# Laser_Teensy_No_AudShield.net
KiCad netlist of a schematic drawn in EAGLE
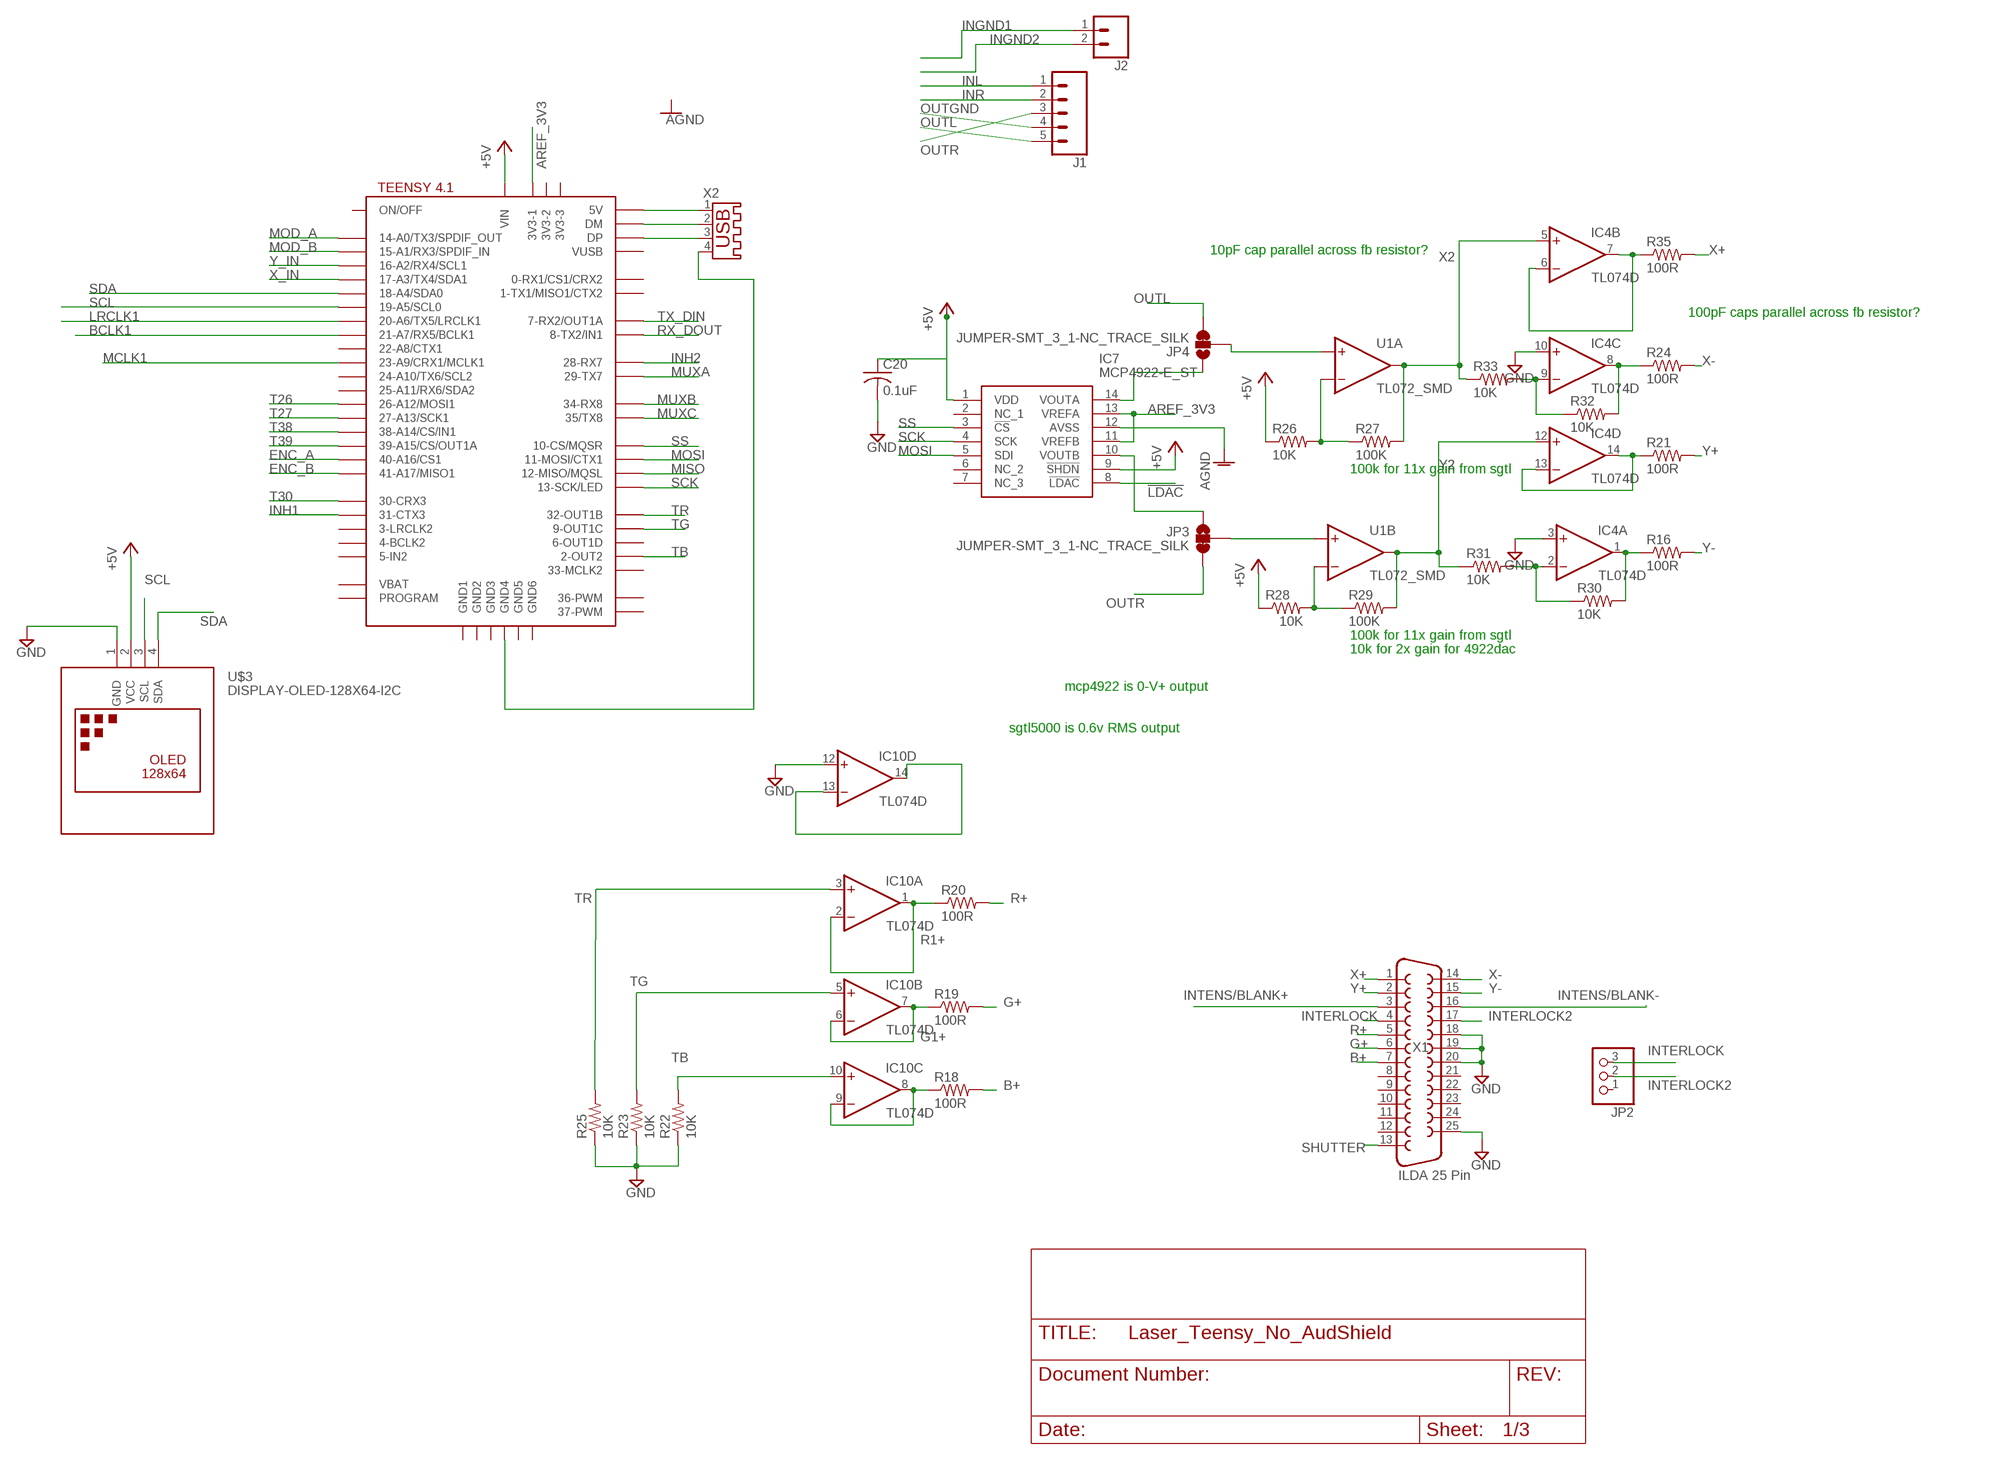
[diagram p0: schematic, sheet 1]
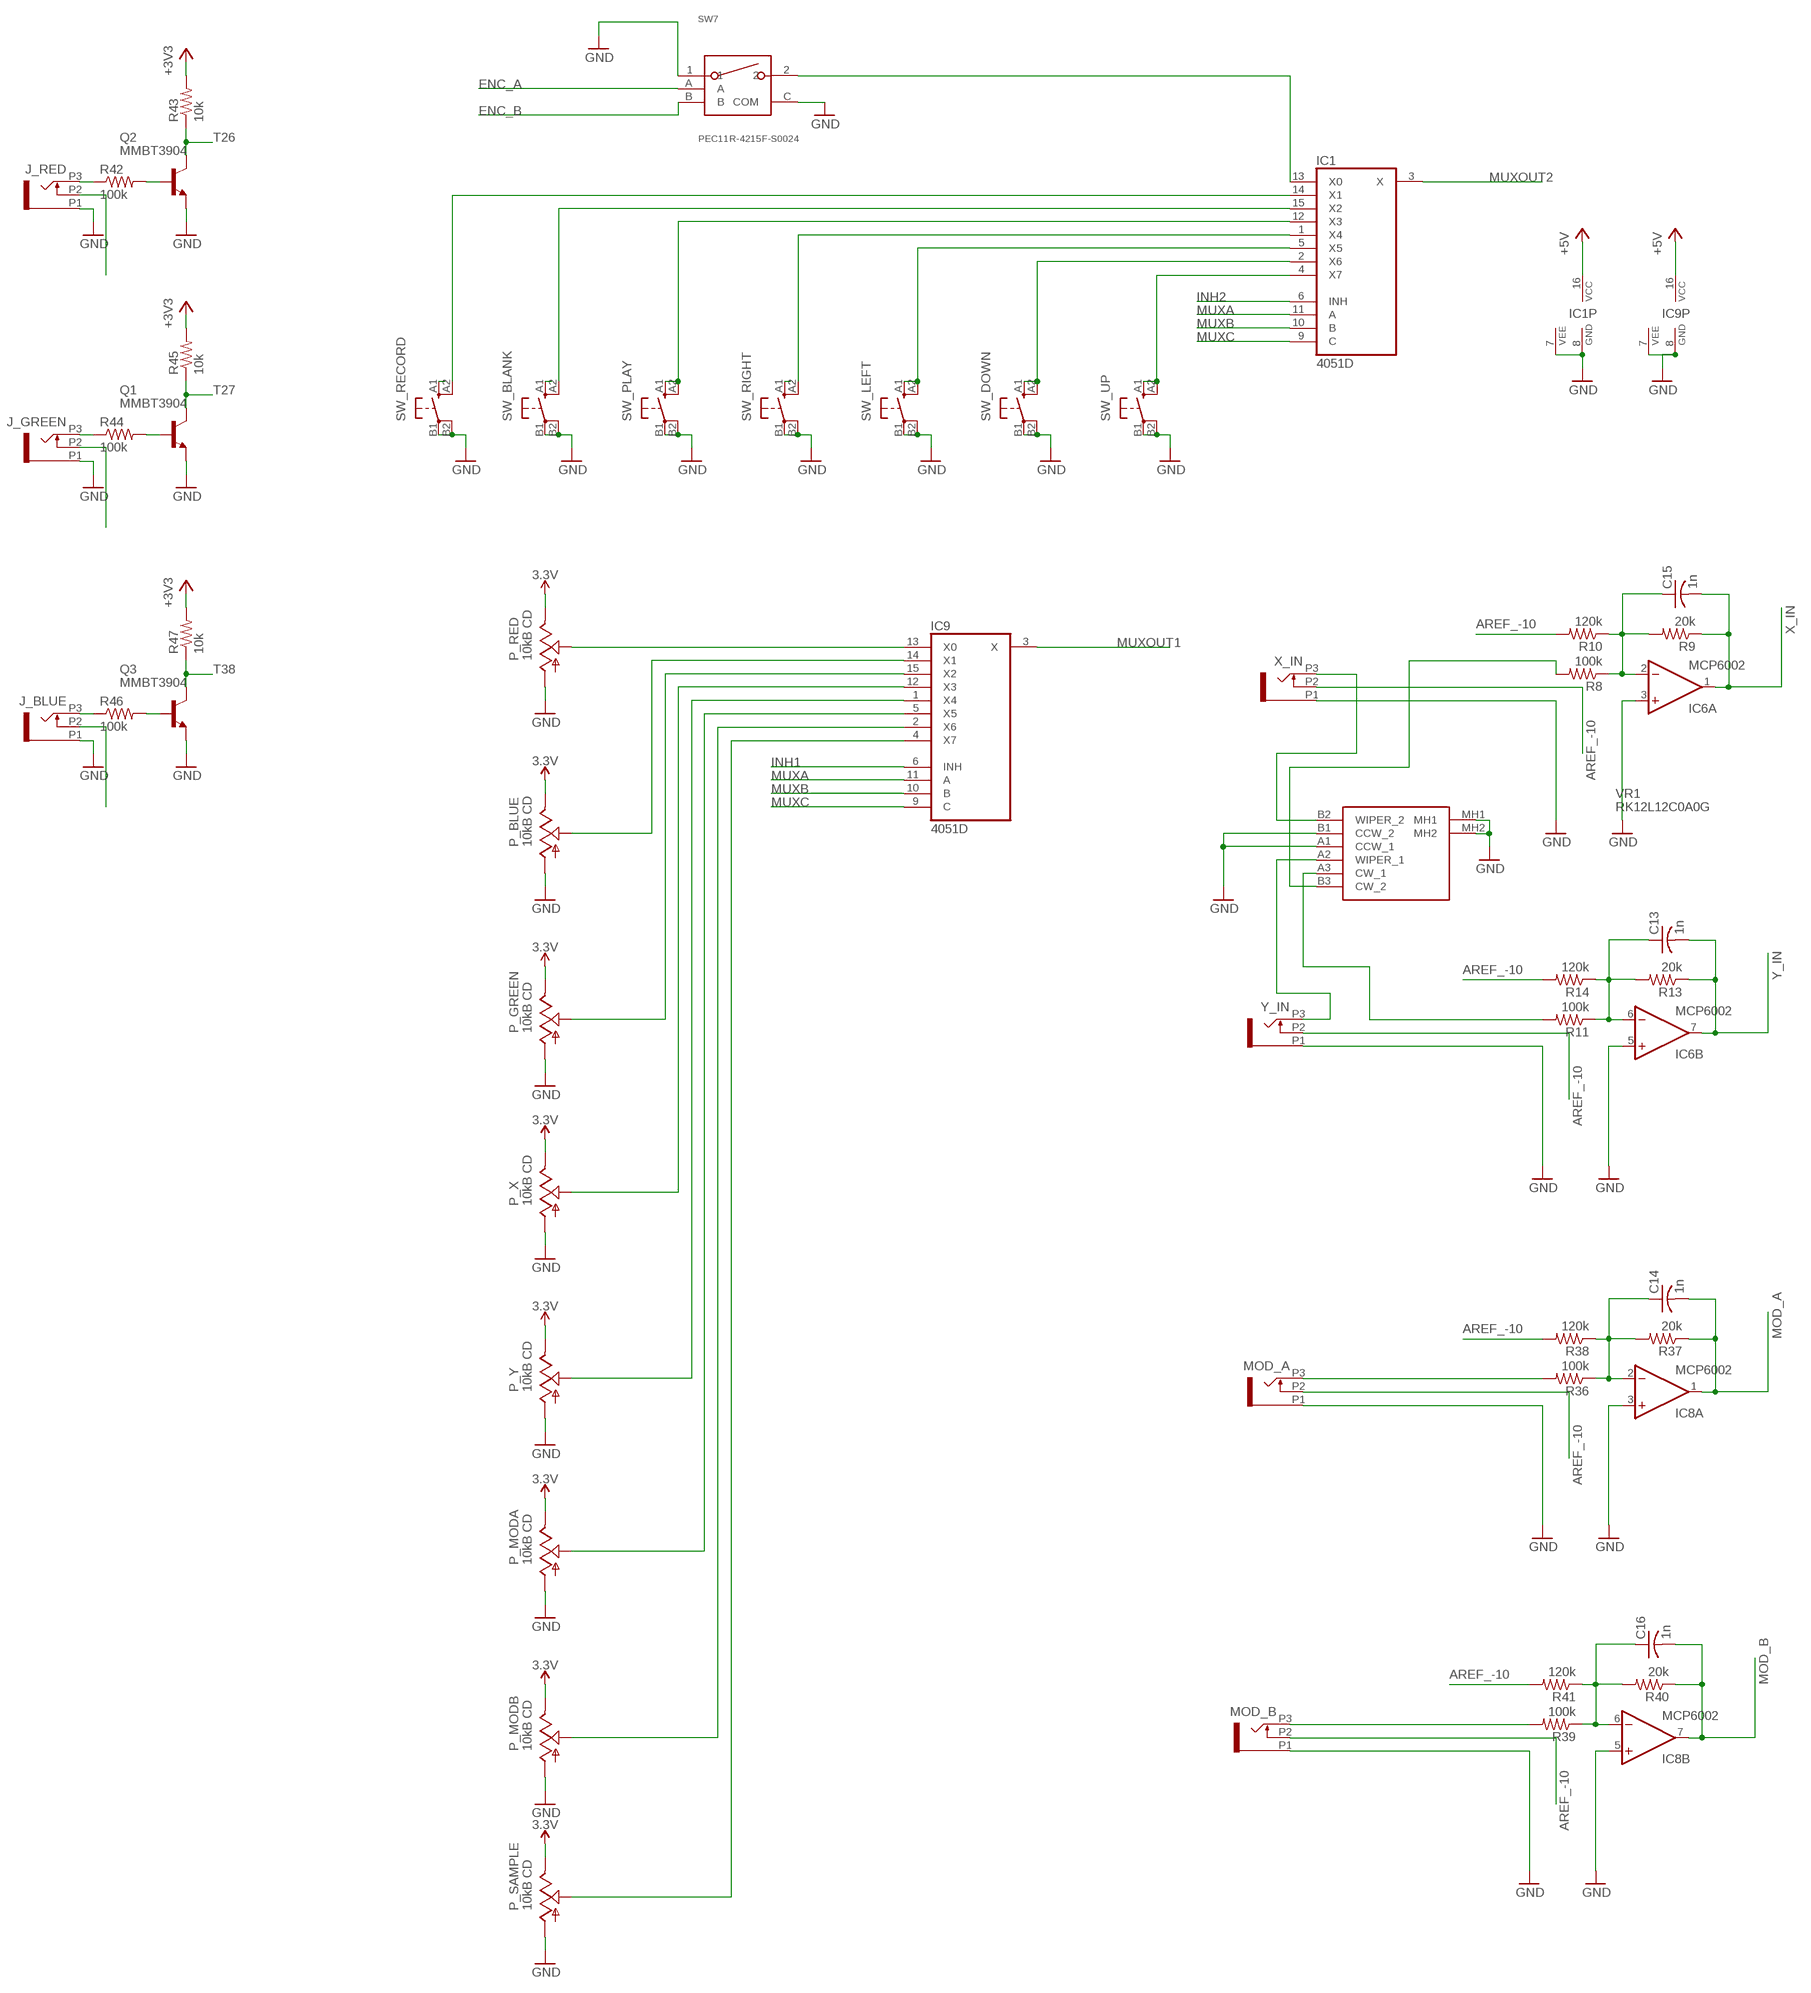
[diagram p1: schematic, sheet 2]
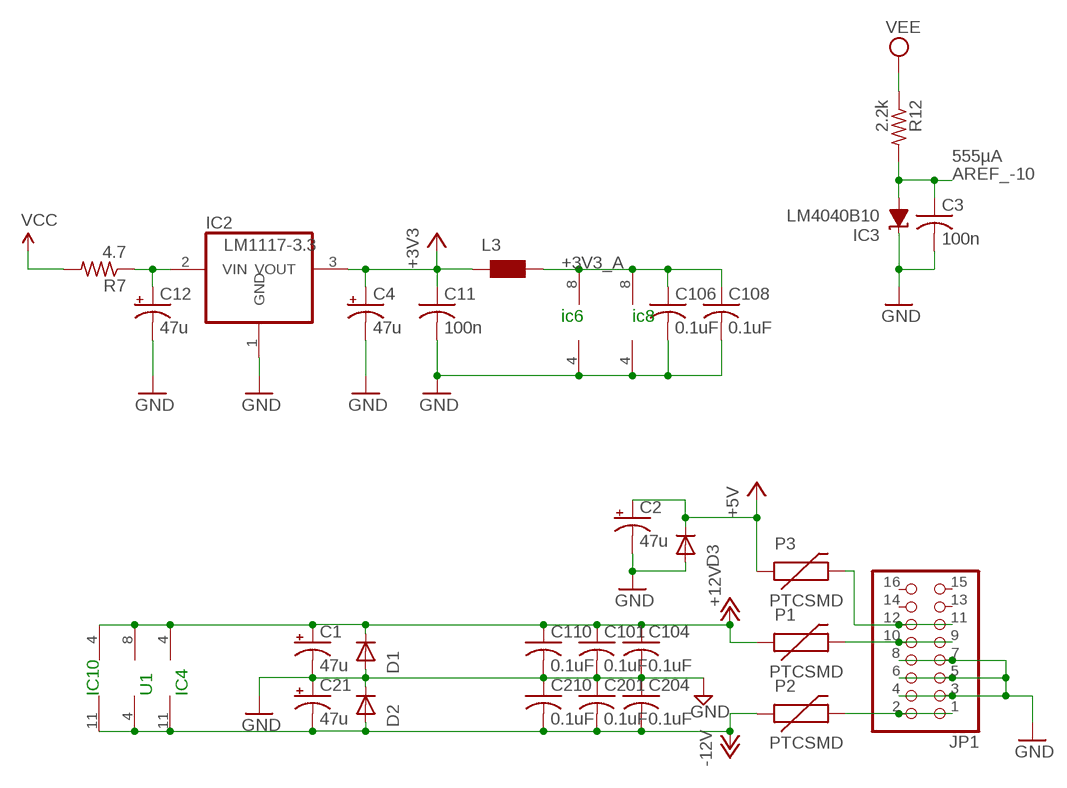
[diagram p2: schematic, sheet 3]

(export (version "E")
  (design (tool "Eeschema 10.0.6"))
  (components
    (comp (ref "C13")
      (value "1n")
      (footprint "eagle-import:C050-025X075")
      (libsource (lib "eagle-import") (part "rcl_334_C-US050-025X075"))
    )
    (comp (ref "C14")
      (value "1n")
      (footprint "eagle-import:C050-025X075")
      (libsource (lib "eagle-import") (part "rcl_334_C-US050-025X075"))
    )
    (comp (ref "C15")
      (value "1n")
      (footprint "eagle-import:C050-025X075")
      (libsource (lib "eagle-import") (part "rcl_334_C-US050-025X075"))
    )
    (comp (ref "C16")
      (value "1n")
      (footprint "eagle-import:C050-025X075")
      (libsource (lib "eagle-import") (part "rcl_334_C-US050-025X075"))
    )
    (comp (ref "IC1")
      (value "4051D")
      (footprint "eagle-import:SO16")
      (libsource (lib "eagle-import") (part "4051D"))
    )
    (comp (ref "IC6")
      (value "MCP6002")
      (footprint "eagle-import:SO08")
      (libsource (lib "eagle-import") (part "TL072D"))
    )
    (comp (ref "IC8")
      (value "MCP6002")
      (footprint "eagle-import:SO08")
      (libsource (lib "eagle-import") (part "TL072D"))
    )
    (comp (ref "IC9")
      (value "4051D")
      (footprint "eagle-import:SO16")
      (libsource (lib "eagle-import") (part "4051D"))
    )
    (comp (ref "J_BLUE")
      (value "PJ301_THONKICONN6")
      (footprint "eagle-import:WQP_PJ_301M6")
      (libsource (lib "eagle-import") (part "PJ301_THONKICONN6"))
    )
    (comp (ref "J_GREEN")
      (value "PJ301_THONKICONN6")
      (footprint "eagle-import:WQP_PJ_301M6")
      (libsource (lib "eagle-import") (part "PJ301_THONKICONN6"))
    )
    (comp (ref "J_RED")
      (value "PJ301_THONKICONN6")
      (footprint "eagle-import:WQP_PJ_301M6")
      (libsource (lib "eagle-import") (part "PJ301_THONKICONN6"))
    )
    (comp (ref "MOD_A")
      (value "PJ301_THONKICONN6")
      (footprint "eagle-import:WQP_PJ_301M6")
      (libsource (lib "eagle-import") (part "og-pj301_variations_PJ301_THONKICONN6"))
    )
    (comp (ref "MOD_B")
      (value "PJ301_THONKICONN6")
      (footprint "eagle-import:WQP_PJ_301M6")
      (libsource (lib "eagle-import") (part "og-pj301_variations_PJ301_THONKICONN6"))
    )
    (comp (ref "P_BLUE")
      (value "10kB CD")
      (footprint "eagle-import:ALPS_POT_VERTICAL_PS")
      (libsource (lib "eagle-import") (part "POT_USVERTICAL_PS"))
    )
    (comp (ref "P_GREEN")
      (value "10kB CD")
      (footprint "eagle-import:ALPS_POT_VERTICAL_PS")
      (libsource (lib "eagle-import") (part "POT_USVERTICAL_PS"))
    )
    (comp (ref "P_MODA")
      (value "10kB CD")
      (footprint "eagle-import:ALPS_POT_VERTICAL_PS")
      (libsource (lib "eagle-import") (part "POT_USVERTICAL_PS"))
    )
    (comp (ref "P_MODB")
      (value "10kB CD")
      (footprint "eagle-import:ALPS_POT_VERTICAL_PS")
      (libsource (lib "eagle-import") (part "POT_USVERTICAL_PS"))
    )
    (comp (ref "P_RED")
      (value "10kB CD")
      (footprint "eagle-import:ALPS_POT_VERTICAL_PS")
      (libsource (lib "eagle-import") (part "POT_USVERTICAL_PS"))
    )
    (comp (ref "P_SAMPLE")
      (value "10kB CD")
      (footprint "eagle-import:ALPS_POT_VERTICAL_PS")
      (libsource (lib "eagle-import") (part "POT_USVERTICAL_PS"))
    )
    (comp (ref "P_X")
      (value "10kB CD")
      (footprint "eagle-import:ALPS_POT_VERTICAL_PS")
      (libsource (lib "eagle-import") (part "POT_USVERTICAL_PS"))
    )
    (comp (ref "P_Y")
      (value "10kB CD")
      (footprint "eagle-import:ALPS_POT_VERTICAL_PS")
      (libsource (lib "eagle-import") (part "POT_USVERTICAL_PS"))
    )
    (comp (ref "Q1")
      (value "MMBT3904")
      (footprint "eagle-import:SOT23-BEC")
      (libsource (lib "eagle-import") (part "-NPN-SOT23-BECMMBT3904LT1"))
    )
    (comp (ref "Q2")
      (value "MMBT3904")
      (footprint "eagle-import:SOT23-BEC")
      (libsource (lib "eagle-import") (part "-NPN-SOT23-BECMMBT3904LT1"))
    )
    (comp (ref "Q3")
      (value "MMBT3904")
      (footprint "eagle-import:SOT23-BEC")
      (libsource (lib "eagle-import") (part "-NPN-SOT23-BECMMBT3904LT1"))
    )
    (comp (ref "R8")
      (value "100k")
      (footprint "eagle-import:0204_7")
      (libsource (lib "eagle-import") (part "rcl_334_R-US_0204/7"))
    )
    (comp (ref "R9")
      (value "20k")
      (footprint "eagle-import:0204_7")
      (libsource (lib "eagle-import") (part "rcl_334_R-US_0204/7"))
    )
    (comp (ref "R10")
      (value "120k")
      (footprint "eagle-import:0204_7")
      (libsource (lib "eagle-import") (part "rcl_334_R-US_0204/7"))
    )
    (comp (ref "R11")
      (value "100k")
      (footprint "eagle-import:0204_7")
      (libsource (lib "eagle-import") (part "rcl_334_R-US_0204/7"))
    )
    (comp (ref "R13")
      (value "20k")
      (footprint "eagle-import:0204_7")
      (libsource (lib "eagle-import") (part "rcl_334_R-US_0204/7"))
    )
    (comp (ref "R14")
      (value "120k")
      (footprint "eagle-import:0204_7")
      (libsource (lib "eagle-import") (part "rcl_334_R-US_0204/7"))
    )
    (comp (ref "R36")
      (value "100k")
      (footprint "eagle-import:0204_7")
      (libsource (lib "eagle-import") (part "rcl_334_R-US_0204/7"))
    )
    (comp (ref "R37")
      (value "20k")
      (footprint "eagle-import:0204_7")
      (libsource (lib "eagle-import") (part "rcl_334_R-US_0204/7"))
    )
    (comp (ref "R38")
      (value "120k")
      (footprint "eagle-import:0204_7")
      (libsource (lib "eagle-import") (part "rcl_334_R-US_0204/7"))
    )
    (comp (ref "R39")
      (value "100k")
      (footprint "eagle-import:0204_7")
      (libsource (lib "eagle-import") (part "rcl_334_R-US_0204/7"))
    )
    (comp (ref "R40")
      (value "20k")
      (footprint "eagle-import:0204_7")
      (libsource (lib "eagle-import") (part "rcl_334_R-US_0204/7"))
    )
    (comp (ref "R41")
      (value "120k")
      (footprint "eagle-import:0204_7")
      (libsource (lib "eagle-import") (part "rcl_334_R-US_0204/7"))
    )
    (comp (ref "R42")
      (value "100k")
      (footprint "eagle-import:R0603")
      (libsource (lib "eagle-import") (part "R-US_R0603"))
    )
    (comp (ref "R43")
      (value "10k")
      (footprint "eagle-import:R0603")
      (libsource (lib "eagle-import") (part "R-US_R0603"))
    )
    (comp (ref "R44")
      (value "100k")
      (footprint "eagle-import:R0603")
      (libsource (lib "eagle-import") (part "R-US_R0603"))
    )
    (comp (ref "R45")
      (value "10k")
      (footprint "eagle-import:R0603")
      (libsource (lib "eagle-import") (part "R-US_R0603"))
    )
    (comp (ref "R46")
      (value "100k")
      (footprint "eagle-import:R0603")
      (libsource (lib "eagle-import") (part "R-US_R0603"))
    )
    (comp (ref "R47")
      (value "10k")
      (footprint "eagle-import:R0603")
      (libsource (lib "eagle-import") (part "R-US_R0603"))
    )
    (comp (ref "SW7")
      (value "PEC11R-4215F-S0024")
      (footprint "eagle-import:PEC11R-4215F-S0024")
      (fields
        (field (name "DIGIKEY_PART_NUMBER") "PEC11R-4215F-S0024-ND")
        (field (name "MANUFACTURER") "Bourns Inc.")
        (field (name "CREATED_BY") "PCBLayout.com")
      )
      (libsource (lib "eagle-import") (part "PEC11R-4215F-S0024"))
    )
    (comp (ref "SW_BLANK")
      (value "D6R")
      (footprint "eagle-import:D6R")
      (libsource (lib "eagle-import") (part "D6R"))
    )
    (comp (ref "SW_DOWN")
      (value "D6R")
      (footprint "eagle-import:D6R")
      (libsource (lib "eagle-import") (part "D6R"))
    )
    (comp (ref "SW_LEFT")
      (value "D6R")
      (footprint "eagle-import:D6R")
      (libsource (lib "eagle-import") (part "D6R"))
    )
    (comp (ref "SW_PLAY")
      (value "D6R")
      (footprint "eagle-import:D6R")
      (libsource (lib "eagle-import") (part "D6R"))
    )
    (comp (ref "SW_RECORD")
      (value "D6R")
      (footprint "eagle-import:D6R")
      (libsource (lib "eagle-import") (part "D6R"))
    )
    (comp (ref "SW_RIGHT")
      (value "D6R")
      (footprint "eagle-import:D6R")
      (libsource (lib "eagle-import") (part "D6R"))
    )
    (comp (ref "SW_UP")
      (value "D6R")
      (footprint "eagle-import:D6R")
      (libsource (lib "eagle-import") (part "D6R"))
    )
    (comp (ref "VR1")
      (value "RK12L12C0A0G")
      (footprint "eagle-import:RK12L12C0A0G")
      (fields (field (name "MOUSER_PART_NUMBER") "688-RK12L12C0A0G"))
      (libsource (lib "eagle-import") (part "RK12L12C0A0G"))
    )
    (comp (ref "X_IN")
      (value "PJ301_THONKICONN6")
      (footprint "eagle-import:WQP_PJ_301M6")
      (libsource (lib "eagle-import") (part "og-pj301_variations_PJ301_THONKICONN6"))
    )
    (comp (ref "Y_IN")
      (value "PJ301_THONKICONN6")
      (footprint "eagle-import:WQP_PJ_301M6")
      (libsource (lib "eagle-import") (part "og-pj301_variations_PJ301_THONKICONN6"))
    )
    (comp (ref "C20")
      (value "0.1uF")
      (footprint "eagle-import:C0603")
      (libsource (lib "eagle-import") (part "C-USC0603"))
    )
    (comp (ref "IC4")
      (value "TL074D")
      (footprint "eagle-import:SO14")
      (libsource (lib "eagle-import") (part "TL074D"))
    )
    (comp (ref "IC7")
      (value "MCP4922-E_ST")
      (footprint "eagle-import:SOP65P638X110-14N")
      (fields
        (field (name "ARROW_PART_NUMBER") "MCP4922-E/ST")
        (field (name "MOUSER_PART_NUMBER") "579-MCP4922-E/ST")
      )
      (libsource (lib "eagle-import") (part "MCP4922-E_ST"))
    )
    (comp (ref "IC10")
      (value "TL074D")
      (footprint "eagle-import:SO14")
      (libsource (lib "eagle-import") (part "TL074D"))
    )
    (comp (ref "J1")
      (value "CONN_05")
      (footprint "eagle-import:1X05")
      (libsource (lib "eagle-import") (part "CONN_05"))
    )
    (comp (ref "J2")
      (value "CONN_02")
      (footprint "eagle-import:1X02")
      (libsource (lib "eagle-import") (part "CONN_02"))
    )
    (comp (ref "JP2")
      (value "PINHD-1X3")
      (footprint "eagle-import:1X03")
      (libsource (lib "eagle-import") (part "PINHD-1X3"))
    )
    (comp (ref "JP3")
      (value "JUMPER-SMT_3_1-NC_TRACE_SILK")
      (footprint "eagle-import:SMT-JUMPER_3_1-NC_TRACE_SILK")
      (libsource (lib "eagle-import") (part "JUMPER-SMT_3_1-NC_TRACE_SILK"))
    )
    (comp (ref "JP4")
      (value "JUMPER-SMT_3_1-NC_TRACE_SILK")
      (footprint "eagle-import:SMT-JUMPER_3_1-NC_TRACE_SILK")
      (libsource (lib "eagle-import") (part "JUMPER-SMT_3_1-NC_TRACE_SILK"))
    )
    (comp (ref "R16")
      (value "100R")
      (footprint "eagle-import:R0603")
      (libsource (lib "eagle-import") (part "resistor_R-US_R0603"))
    )
    (comp (ref "R18")
      (value "100R")
      (footprint "eagle-import:R0603")
      (libsource (lib "eagle-import") (part "resistor_R-US_R0603"))
    )
    (comp (ref "R19")
      (value "100R")
      (footprint "eagle-import:R0603")
      (libsource (lib "eagle-import") (part "resistor_R-US_R0603"))
    )
    (comp (ref "R20")
      (value "100R")
      (footprint "eagle-import:R0603")
      (libsource (lib "eagle-import") (part "resistor_R-US_R0603"))
    )
    (comp (ref "R21")
      (value "100R")
      (footprint "eagle-import:R0603")
      (libsource (lib "eagle-import") (part "resistor_R-US_R0603"))
    )
    (comp (ref "R22")
      (value "10K")
      (footprint "eagle-import:R0603")
      (libsource (lib "eagle-import") (part "resistor_R-US_R0603"))
    )
    (comp (ref "R23")
      (value "10K")
      (footprint "eagle-import:R0603")
      (libsource (lib "eagle-import") (part "resistor_R-US_R0603"))
    )
    (comp (ref "R24")
      (value "100R")
      (footprint "eagle-import:R0603")
      (libsource (lib "eagle-import") (part "resistor_R-US_R0603"))
    )
    (comp (ref "R25")
      (value "10K")
      (footprint "eagle-import:R0603")
      (libsource (lib "eagle-import") (part "resistor_R-US_R0603"))
    )
    (comp (ref "R26")
      (value "10K")
      (footprint "eagle-import:R0603")
      (libsource (lib "eagle-import") (part "resistor_R-US_R0603"))
    )
    (comp (ref "R27")
      (value "100K")
      (footprint "eagle-import:R0603")
      (libsource (lib "eagle-import") (part "resistor_R-US_R0603"))
    )
    (comp (ref "R28")
      (value "10K")
      (footprint "eagle-import:R0603")
      (libsource (lib "eagle-import") (part "resistor_R-US_R0603"))
    )
    (comp (ref "R29")
      (value "100K")
      (footprint "eagle-import:R0603")
      (libsource (lib "eagle-import") (part "resistor_R-US_R0603"))
    )
    (comp (ref "R30")
      (value "10K")
      (footprint "eagle-import:R0603")
      (libsource (lib "eagle-import") (part "resistor_R-US_R0603"))
    )
    (comp (ref "R31")
      (value "10K")
      (footprint "eagle-import:R0603")
      (libsource (lib "eagle-import") (part "resistor_R-US_R0603"))
    )
    (comp (ref "R32")
      (value "10K")
      (footprint "eagle-import:R0603")
      (libsource (lib "eagle-import") (part "resistor_R-US_R0603"))
    )
    (comp (ref "R33")
      (value "10K")
      (footprint "eagle-import:R0603")
      (libsource (lib "eagle-import") (part "resistor_R-US_R0603"))
    )
    (comp (ref "R35")
      (value "100R")
      (footprint "eagle-import:R0603")
      (libsource (lib "eagle-import") (part "resistor_R-US_R0603"))
    )
    (comp (ref "U$2")
      (value "TEENSY41-E")
      (footprint "eagle-import:TENNSY41-E")
      (libsource (lib "eagle-import") (part "TEENSY41-E"))
    )
    (comp (ref "U$3")
      (value "DISPLAY-OLED-128X64-I2C")
      (footprint "eagle-import:DISPLAY-OLED-128X64-I2C")
      (libsource (lib "eagle-import") (part "DISPLAY-OLED-128X64-I2C"))
    )
    (comp (ref "U1")
      (value "TL072_SMD")
      (footprint "eagle-import:SO08")
      (libsource (lib "eagle-import") (part "TL072_SMD"))
    )
    (comp (ref "X1")
      (value "ILDA 25 Pin")
      (footprint "eagle-import:F25D")
      (libsource (lib "eagle-import") (part "F25D"))
    )
    (comp (ref "X2")
      (value "USB-A003")
      (footprint "eagle-import:USB-A003")
      (libsource (lib "eagle-import") (part "USB-A003"))
    )
    (comp (ref "C1")
      (value "47u")
      (footprint "eagle-import:PANASONIC_D")
      (libsource (lib "eagle-import") (part "CPOL-USD"))
    )
    (comp (ref "C2")
      (value "47u")
      (footprint "eagle-import:PANASONIC_D")
      (libsource (lib "eagle-import") (part "CPOL-USD"))
    )
    (comp (ref "C3")
      (value "100n")
      (footprint "eagle-import:C0603")
      (libsource (lib "eagle-import") (part "rcl_C-USC0603"))
    )
    (comp (ref "C4")
      (value "47u")
      (footprint "eagle-import:PANASONIC_D")
      (libsource (lib "eagle-import") (part "CPOL-USD"))
    )
    (comp (ref "C11")
      (value "100n")
      (footprint "eagle-import:C0603")
      (libsource (lib "eagle-import") (part "rcl_C-USC0603"))
    )
    (comp (ref "C12")
      (value "47u")
      (footprint "eagle-import:PANASONIC_D")
      (libsource (lib "eagle-import") (part "CPOL-USD"))
    )
    (comp (ref "C21")
      (value "47u")
      (footprint "eagle-import:PANASONIC_D")
      (libsource (lib "eagle-import") (part "CPOL-USD"))
    )
    (comp (ref "C101")
      (value "0.1uF")
      (footprint "eagle-import:C0603")
      (libsource (lib "eagle-import") (part "C-USC0603"))
    )
    (comp (ref "C104")
      (value "0.1uF")
      (footprint "eagle-import:C0603")
      (libsource (lib "eagle-import") (part "C-USC0603"))
    )
    (comp (ref "C106")
      (value "0.1uF")
      (footprint "eagle-import:C0603")
      (libsource (lib "eagle-import") (part "C-USC0603"))
    )
    (comp (ref "C108")
      (value "0.1uF")
      (footprint "eagle-import:C0603")
      (libsource (lib "eagle-import") (part "C-USC0603"))
    )
    (comp (ref "C110")
      (value "0.1uF")
      (footprint "eagle-import:C0603")
      (libsource (lib "eagle-import") (part "C-USC0603"))
    )
    (comp (ref "C201")
      (value "0.1uF")
      (footprint "eagle-import:C0603")
      (libsource (lib "eagle-import") (part "C-USC0603"))
    )
    (comp (ref "C204")
      (value "0.1uF")
      (footprint "eagle-import:C0603")
      (libsource (lib "eagle-import") (part "C-USC0603"))
    )
    (comp (ref "C210")
      (value "0.1uF")
      (footprint "eagle-import:C0603")
      (libsource (lib "eagle-import") (part "C-USC0603"))
    )
    (comp (ref "D1")
      (value "1N5819HW")
      (footprint "eagle-import:SOD123")
      (libsource (lib "eagle-import") (part "DIODE-SOD123"))
    )
    (comp (ref "D2")
      (value "1N5819HW")
      (footprint "eagle-import:SOD123")
      (libsource (lib "eagle-import") (part "DIODE-SOD123"))
    )
    (comp (ref "D3")
      (value "1N5819HW")
      (footprint "eagle-import:SOD123")
      (libsource (lib "eagle-import") (part "DIODE-SOD123"))
    )
    (comp (ref "IC2")
      (value "LM1117-3.3")
      (footprint "eagle-import:TO252")
      (libsource (lib "eagle-import") (part "REG1117T"))
    )
    (comp (ref "IC3")
      (value "LM4040B10")
      (footprint "eagle-import:DBZ_R-PDSO-G3")
      (libsource (lib "eagle-import") (part "LM4041DBZB12"))
    )
    (comp (ref "JP1")
      (value "PINHD-2X8")
      (footprint "eagle-import:2X08")
      (libsource (lib "eagle-import") (part "PINHD-2X8"))
    )
    (comp (ref "L3")
      (value "WE-CBF_0603")
      (footprint "eagle-import:0603")
      (libsource (lib "eagle-import") (part "WE-CBF_0603"))
    )
    (comp (ref "P1")
      (value "PTCSMD")
      (footprint "eagle-import:PTC-1206")
      (libsource (lib "eagle-import") (part "PTCSMD"))
    )
    (comp (ref "P2")
      (value "PTCSMD")
      (footprint "eagle-import:PTC-1206")
      (libsource (lib "eagle-import") (part "PTCSMD"))
    )
    (comp (ref "P3")
      (value "PTCSMD")
      (footprint "eagle-import:PTC-1206")
      (libsource (lib "eagle-import") (part "PTCSMD"))
    )
    (comp (ref "R7")
      (value "4.7")
      (footprint "eagle-import:R1206")
      (libsource (lib "eagle-import") (part "R-US_R1206"))
    )
    (comp (ref "R12")
      (value "2.2k")
      (footprint "eagle-import:R0603")
      (libsource (lib "eagle-import") (part "R-US_R0603"))
    )
  )
  (nets
    (net (code "1") (name "+3V3") (class "Default")
      (node (ref "C11") (pin "1") (pinfunction "1_1") (pintype "passive"))
      (node (ref "C4") (pin "+") (pinfunction "+_+") (pintype "passive"))
      (node (ref "IC2") (pin "3") (pinfunction "VOUT_3") (pintype "output"))
      (node (ref "L3") (pin "1") (pinfunction "1_1") (pintype "passive"))
      (node (ref "R43") (pin "2") (pinfunction "2_2") (pintype "passive"))
      (node (ref "R45") (pin "2") (pinfunction "2_2") (pintype "passive"))
      (node (ref "R47") (pin "2") (pinfunction "2_2") (pintype "passive"))
    )
    (net (code "2") (name "+3V3_A") (class "Default")
      (node (ref "C106") (pin "1") (pinfunction "1_1") (pintype "passive"))
      (node (ref "C108") (pin "1") (pinfunction "1_1") (pintype "passive"))
      (node (ref "IC6") (pin "8") (pinfunction "V+_8") (pintype "power_in"))
      (node (ref "IC8") (pin "8") (pinfunction "V+_8") (pintype "power_in"))
      (node (ref "L3") (pin "2") (pinfunction "2_2") (pintype "passive"))
    )
    (net (code "3") (name "+5V") (class "Default")
      (node (ref "C2") (pin "+") (pinfunction "+_+") (pintype "passive"))
      (node (ref "C20") (pin "1") (pinfunction "1_1") (pintype "passive"))
      (node (ref "D3") (pin "C") (pinfunction "C_C") (pintype "passive"))
      (node (ref "IC1") (pin "16") (pinfunction "VCC_16") (pintype "power_in"))
      (node (ref "IC7") (pin "1") (pinfunction "VDD_1") (pintype "bidirectional"))
      (node (ref "IC7") (pin "9") (pinfunction "~{SHDN}_9") (pintype "bidirectional"))
      (node (ref "IC9") (pin "16") (pinfunction "VCC_16") (pintype "power_in"))
      (node (ref "P3") (pin "1") (pinfunction "1_1") (pintype "bidirectional"))
      (node (ref "R26") (pin "1") (pinfunction "1_1") (pintype "passive"))
      (node (ref "R28") (pin "1") (pinfunction "1_1") (pintype "passive"))
      (node (ref "U$2") (pin "VIN") (pinfunction "VIN_VIN") (pintype "bidirectional"))
      (node (ref "U$3") (pin "2") (pinfunction "VCC_2") (pintype "power_in"))
    )
    (net (code "4") (name "+12V") (class "Default")
      (node (ref "C1") (pin "+") (pinfunction "+_+") (pintype "passive"))
      (node (ref "C101") (pin "1") (pinfunction "1_1") (pintype "passive"))
      (node (ref "C104") (pin "1") (pinfunction "1_1") (pintype "passive"))
      (node (ref "C110") (pin "1") (pinfunction "1_1") (pintype "passive"))
      (node (ref "D1") (pin "C") (pinfunction "C_C") (pintype "passive"))
      (node (ref "IC10") (pin "4") (pinfunction "V+_4") (pintype "power_in"))
      (node (ref "IC4") (pin "4") (pinfunction "V+_4") (pintype "power_in"))
      (node (ref "P1") (pin "1") (pinfunction "1_1") (pintype "bidirectional"))
      (node (ref "U1") (pin "8") (pinfunction "V+_8") (pintype "power_in"))
    )
    (net (code "5") (name "-12V") (class "Default")
      (node (ref "C201") (pin "2") (pinfunction "2_2") (pintype "passive"))
      (node (ref "C204") (pin "2") (pinfunction "2_2") (pintype "passive"))
      (node (ref "C21") (pin "-") (pinfunction "-_-") (pintype "passive"))
      (node (ref "C210") (pin "2") (pinfunction "2_2") (pintype "passive"))
      (node (ref "D2") (pin "A") (pinfunction "A_A") (pintype "passive"))
      (node (ref "IC10") (pin "11") (pinfunction "V-_11") (pintype "power_in"))
      (node (ref "IC4") (pin "11") (pinfunction "V-_11") (pintype "power_in"))
      (node (ref "P2") (pin "1") (pinfunction "1_1") (pintype "bidirectional"))
      (node (ref "U1") (pin "4") (pinfunction "V-_4") (pintype "power_in"))
    )
    (net (code "6") (name "3.3V") (class "Default")
      (node (ref "P_BLUE") (pin "P$1") (pinfunction "E_P$1") (pintype "passive"))
      (node (ref "P_GREEN") (pin "P$1") (pinfunction "E_P$1") (pintype "passive"))
      (node (ref "P_MODA") (pin "P$1") (pinfunction "E_P$1") (pintype "passive"))
      (node (ref "P_MODB") (pin "P$1") (pinfunction "E_P$1") (pintype "passive"))
      (node (ref "P_RED") (pin "P$1") (pinfunction "E_P$1") (pintype "passive"))
      (node (ref "P_SAMPLE") (pin "P$1") (pinfunction "E_P$1") (pintype "passive"))
      (node (ref "P_X") (pin "P$1") (pinfunction "E_P$1") (pintype "passive"))
      (node (ref "P_Y") (pin "P$1") (pinfunction "E_P$1") (pintype "passive"))
    )
    (net (code "7") (name "AGND") (class "Default")
      (node (ref "IC7") (pin "12") (pinfunction "AVSS_12") (pintype "bidirectional"))
    )
    (net (code "8") (name "AREF_-10") (class "Default")
      (node (ref "C3") (pin "1") (pinfunction "1_1") (pintype "passive"))
      (node (ref "IC3") (pin "2") (pinfunction "A_2") (pintype "passive"))
      (node (ref "MOD_A") (pin "P2") (pinfunction "2_P2") (pintype "passive"))
      (node (ref "MOD_B") (pin "P2") (pinfunction "2_P2") (pintype "passive"))
      (node (ref "R10") (pin "2") (pinfunction "2_2") (pintype "passive"))
      (node (ref "R12") (pin "2") (pinfunction "2_2") (pintype "passive"))
      (node (ref "R14") (pin "2") (pinfunction "2_2") (pintype "passive"))
      (node (ref "R38") (pin "2") (pinfunction "2_2") (pintype "passive"))
      (node (ref "R41") (pin "2") (pinfunction "2_2") (pintype "passive"))
      (node (ref "X_IN") (pin "P2") (pinfunction "2_P2") (pintype "passive"))
      (node (ref "Y_IN") (pin "P2") (pinfunction "2_P2") (pintype "passive"))
    )
    (net (code "9") (name "AREF_3V3") (class "Default")
      (node (ref "IC7") (pin "11") (pinfunction "VREFB_11") (pintype "bidirectional"))
      (node (ref "IC7") (pin "13") (pinfunction "VREFA_13") (pintype "bidirectional"))
      (node (ref "U$2") (pin "3V3-1") (pinfunction "3V3-1_3V3-1") (pintype "bidirectional"))
    )
    (net (code "10") (name "B+") (class "Default")
      (node (ref "R18") (pin "2") (pinfunction "2_2") (pintype "passive"))
      (node (ref "X1") (pin "7") (pinfunction "7_7") (pintype "passive"))
    )
    (net (code "11") (name "BCLK1") (class "Default")
      (node (ref "U$2") (pin "21-A7/RX5/BCLK1") (pinfunction "21-A7/RX5/BCLK1_21-A7/RX5/BCLK1") (pintype "bidirectional"))
    )
    (net (code "12") (name "ENC_A") (class "Default")
      (node (ref "SW7") (pin "A") (pinfunction "A_A") (pintype "passive"))
      (node (ref "U$2") (pin "40-A16/CS1") (pinfunction "40-A16/CS1_40-A16/CS1") (pintype "bidirectional"))
    )
    (net (code "13") (name "ENC_B") (class "Default")
      (node (ref "SW7") (pin "B") (pinfunction "B_B") (pintype "passive"))
      (node (ref "U$2") (pin "41-A17/MISO1") (pinfunction "41-A17/MISO1_41-A17/MISO1") (pintype "bidirectional"))
    )
    (net (code "14") (name "G+") (class "Default")
      (node (ref "R19") (pin "2") (pinfunction "2_2") (pintype "passive"))
      (node (ref "X1") (pin "6") (pinfunction "6_6") (pintype "passive"))
    )
    (net (code "15") (name "G1+") (class "Default")
      (node (ref "IC10") (pin "6") (pinfunction "-IN_6") (pintype "input"))
      (node (ref "IC10") (pin "7") (pinfunction "OUT_7") (pintype "output"))
      (node (ref "R19") (pin "1") (pinfunction "1_1") (pintype "passive"))
    )
    (net (code "16") (name "GND") (class "Default")
      (node (ref "C1") (pin "-") (pinfunction "-_-") (pintype "passive"))
      (node (ref "C101") (pin "2") (pinfunction "2_2") (pintype "passive"))
      (node (ref "C104") (pin "2") (pinfunction "2_2") (pintype "passive"))
      (node (ref "C106") (pin "2") (pinfunction "2_2") (pintype "passive"))
      (node (ref "C108") (pin "2") (pinfunction "2_2") (pintype "passive"))
      (node (ref "C11") (pin "2") (pinfunction "2_2") (pintype "passive"))
      (node (ref "C110") (pin "2") (pinfunction "2_2") (pintype "passive"))
      (node (ref "C12") (pin "-") (pinfunction "-_-") (pintype "passive"))
      (node (ref "C2") (pin "-") (pinfunction "-_-") (pintype "passive"))
      (node (ref "C20") (pin "2") (pinfunction "2_2") (pintype "passive"))
      (node (ref "C201") (pin "1") (pinfunction "1_1") (pintype "passive"))
      (node (ref "C204") (pin "1") (pinfunction "1_1") (pintype "passive"))
      (node (ref "C21") (pin "+") (pinfunction "+_+") (pintype "passive"))
      (node (ref "C210") (pin "1") (pinfunction "1_1") (pintype "passive"))
      (node (ref "C3") (pin "2") (pinfunction "2_2") (pintype "passive"))
      (node (ref "C4") (pin "-") (pinfunction "-_-") (pintype "passive"))
      (node (ref "D1") (pin "A") (pinfunction "A_A") (pintype "passive"))
      (node (ref "D2") (pin "C") (pinfunction "C_C") (pintype "passive"))
      (node (ref "D3") (pin "A") (pinfunction "A_A") (pintype "passive"))
      (node (ref "IC1") (pin "7") (pinfunction "VEE_7") (pintype "power_in"))
      (node (ref "IC1") (pin "8") (pinfunction "GND_8") (pintype "power_in"))
      (node (ref "IC10") (pin "12") (pinfunction "+IN_12") (pintype "input"))
      (node (ref "IC2") (pin "1") (pinfunction "GND_1") (pintype "power_in"))
      (node (ref "IC3") (pin "1") (pinfunction "C_1") (pintype "passive"))
      (node (ref "IC4") (pin "10") (pinfunction "+IN_10") (pintype "input"))
      (node (ref "IC4") (pin "3") (pinfunction "+IN_3") (pintype "input"))
      (node (ref "IC6") (pin "3") (pinfunction "+IN_3") (pintype "input"))
      (node (ref "IC6") (pin "4") (pinfunction "V-_4") (pintype "power_in"))
      (node (ref "IC6") (pin "5") (pinfunction "+IN_5") (pintype "input"))
      (node (ref "IC8") (pin "3") (pinfunction "+IN_3") (pintype "input"))
      (node (ref "IC8") (pin "4") (pinfunction "V-_4") (pintype "power_in"))
      (node (ref "IC8") (pin "5") (pinfunction "+IN_5") (pintype "input"))
      (node (ref "IC9") (pin "7") (pinfunction "VEE_7") (pintype "power_in"))
      (node (ref "IC9") (pin "8") (pinfunction "GND_8") (pintype "power_in"))
      (node (ref "JP1") (pin "3") (pinfunction "3_3") (pintype "passive"))
      (node (ref "JP1") (pin "4") (pinfunction "4_4") (pintype "passive"))
      (node (ref "JP1") (pin "5") (pinfunction "5_5") (pintype "passive"))
      (node (ref "JP1") (pin "6") (pinfunction "6_6") (pintype "passive"))
      (node (ref "JP1") (pin "7") (pinfunction "7_7") (pintype "passive"))
      (node (ref "JP1") (pin "8") (pinfunction "8_8") (pintype "passive"))
      (node (ref "J_BLUE") (pin "P1") (pinfunction "1_P1") (pintype "passive"))
      (node (ref "J_GREEN") (pin "P1") (pinfunction "1_P1") (pintype "passive"))
      (node (ref "J_RED") (pin "P1") (pinfunction "1_P1") (pintype "passive"))
      (node (ref "MOD_A") (pin "P1") (pinfunction "1_P1") (pintype "passive"))
      (node (ref "MOD_B") (pin "P1") (pinfunction "1_P1") (pintype "passive"))
      (node (ref "P_BLUE") (pin "P$3") (pinfunction "A_P$3") (pintype "passive"))
      (node (ref "P_GREEN") (pin "P$3") (pinfunction "A_P$3") (pintype "passive"))
      (node (ref "P_MODA") (pin "P$3") (pinfunction "A_P$3") (pintype "passive"))
      (node (ref "P_MODB") (pin "P$3") (pinfunction "A_P$3") (pintype "passive"))
      (node (ref "P_RED") (pin "P$3") (pinfunction "A_P$3") (pintype "passive"))
      (node (ref "P_SAMPLE") (pin "P$3") (pinfunction "A_P$3") (pintype "passive"))
      (node (ref "P_X") (pin "P$3") (pinfunction "A_P$3") (pintype "passive"))
      (node (ref "P_Y") (pin "P$3") (pinfunction "A_P$3") (pintype "passive"))
      (node (ref "Q1") (pin "E") (pinfunction "E_E") (pintype "passive"))
      (node (ref "Q2") (pin "E") (pinfunction "E_E") (pintype "passive"))
      (node (ref "Q3") (pin "E") (pinfunction "E_E") (pintype "passive"))
      (node (ref "R22") (pin "1") (pinfunction "1_1") (pintype "passive"))
      (node (ref "R23") (pin "1") (pinfunction "1_1") (pintype "passive"))
      (node (ref "R25") (pin "1") (pinfunction "1_1") (pintype "passive"))
      (node (ref "SW7") (pin "1") (pinfunction "1_1") (pintype "passive"))
      (node (ref "SW7") (pin "C") (pinfunction "COM_C") (pintype "passive"))
      (node (ref "SW_BLANK") (pin "B2") (pinfunction "P1_B2") (pintype "passive"))
      (node (ref "SW_DOWN") (pin "B1") (pinfunction "P_B1") (pintype "passive"))
      (node (ref "SW_DOWN") (pin "B2") (pinfunction "P1_B2") (pintype "passive"))
      (node (ref "SW_LEFT") (pin "B1") (pinfunction "P_B1") (pintype "passive"))
      (node (ref "SW_LEFT") (pin "B2") (pinfunction "P1_B2") (pintype "passive"))
      (node (ref "SW_PLAY") (pin "B1") (pinfunction "P_B1") (pintype "passive"))
      (node (ref "SW_PLAY") (pin "B2") (pinfunction "P1_B2") (pintype "passive"))
      (node (ref "SW_RECORD") (pin "B2") (pinfunction "P1_B2") (pintype "passive"))
      (node (ref "SW_RIGHT") (pin "B2") (pinfunction "P1_B2") (pintype "passive"))
      (node (ref "SW_UP") (pin "B1") (pinfunction "P_B1") (pintype "passive"))
      (node (ref "SW_UP") (pin "B2") (pinfunction "P1_B2") (pintype "passive"))
      (node (ref "U$3") (pin "1") (pinfunction "GND_1") (pintype "power_in"))
      (node (ref "VR1") (pin "A1") (pinfunction "CCW_1_A1") (pintype "bidirectional"))
      (node (ref "VR1") (pin "B1") (pinfunction "CCW_2_B1") (pintype "bidirectional"))
      (node (ref "VR1") (pin "MH1") (pinfunction "MH1_MH1") (pintype "bidirectional"))
      (node (ref "VR1") (pin "MH2") (pinfunction "MH2_MH2") (pintype "bidirectional"))
      (node (ref "X1") (pin "18") (pinfunction "18_18") (pintype "passive"))
      (node (ref "X1") (pin "19") (pinfunction "19_19") (pintype "passive"))
      (node (ref "X1") (pin "20") (pinfunction "20_20") (pintype "passive"))
      (node (ref "X1") (pin "25") (pinfunction "25_25") (pintype "passive"))
      (node (ref "X_IN") (pin "P1") (pinfunction "1_P1") (pintype "passive"))
      (node (ref "Y_IN") (pin "P1") (pinfunction "1_P1") (pintype "passive"))
    )
    (net (code "17") (name "INGND1") (class "Default")
      (node (ref "J2") (pin "1") (pinfunction "1_1") (pintype "passive"))
    )
    (net (code "18") (name "INGND2") (class "Default")
      (node (ref "J2") (pin "2") (pinfunction "2_2") (pintype "passive"))
    )
    (net (code "19") (name "INH1") (class "Default")
      (node (ref "IC9") (pin "6") (pinfunction "INH_6") (pintype "input"))
      (node (ref "U$2") (pin "31-CTX3") (pinfunction "31-CTX3_31-CTX3") (pintype "bidirectional"))
    )
    (net (code "20") (name "INH2") (class "Default")
      (node (ref "IC1") (pin "6") (pinfunction "INH_6") (pintype "input"))
      (node (ref "U$2") (pin "28-RX7") (pinfunction "28-RX7_28-RX7") (pintype "bidirectional"))
    )
    (net (code "21") (name "INL") (class "Default")
      (node (ref "J1") (pin "1") (pinfunction "1_1") (pintype "passive"))
    )
    (net (code "22") (name "INR") (class "Default")
      (node (ref "J1") (pin "2") (pinfunction "2_2") (pintype "passive"))
    )
    (net (code "23") (name "INTENS{slash}BLANK+") (class "Default")
      (node (ref "X1") (pin "3") (pinfunction "3_3") (pintype "passive"))
    )
    (net (code "24") (name "INTENS{slash}BLANK-") (class "Default")
      (node (ref "X1") (pin "16") (pinfunction "16_16") (pintype "passive"))
    )
    (net (code "25") (name "INTERLOCK") (class "Default")
      (node (ref "JP2") (pin "3") (pinfunction "3_3") (pintype "passive"))
      (node (ref "X1") (pin "4") (pinfunction "4_4") (pintype "passive"))
    )
    (net (code "26") (name "INTERLOCK2") (class "Default")
      (node (ref "JP2") (pin "2") (pinfunction "2_2") (pintype "passive"))
      (node (ref "X1") (pin "17") (pinfunction "17_17") (pintype "passive"))
    )
    (net (code "27") (name "LRCLK1") (class "Default")
      (node (ref "U$2") (pin "20-A6/TX5/LRCLK1") (pinfunction "20-A6/TX5/LRCLK1_20-A6/TX5/LRCLK1") (pintype "bidirectional"))
    )
    (net (code "28") (name "MCLK1") (class "Default")
      (node (ref "U$2") (pin "23-A9/CRX1/MCLK1") (pinfunction "23-A9/CRX1/MCLK1_23-A9/CRX1/MCLK1") (pintype "bidirectional"))
    )
    (net (code "29") (name "MISO") (class "Default")
      (node (ref "U$2") (pin "12-MISO/MQSL") (pinfunction "12-MISO/MQSL_12-MISO/MQSL") (pintype "bidirectional"))
    )
    (net (code "30") (name "MOD_A") (class "Default")
      (node (ref "C14") (pin "2") (pinfunction "2_2") (pintype "passive"))
      (node (ref "IC8") (pin "1") (pinfunction "OUT_1") (pintype "output"))
      (node (ref "R37") (pin "1") (pinfunction "1_1") (pintype "passive"))
      (node (ref "U$2") (pin "14-A0/TX3/SPDIF_OUT") (pinfunction "14-A0/TX3/SPDIF_OUT_14-A0/TX3/SPDIF_OUT") (pintype "bidirectional"))
    )
    (net (code "31") (name "MOD_B") (class "Default")
      (node (ref "C16") (pin "2") (pinfunction "2_2") (pintype "passive"))
      (node (ref "IC8") (pin "7") (pinfunction "OUT_7") (pintype "output"))
      (node (ref "R40") (pin "1") (pinfunction "1_1") (pintype "passive"))
      (node (ref "U$2") (pin "15-A1/RX3/SPDIF_IN") (pinfunction "15-A1/RX3/SPDIF_IN_15-A1/RX3/SPDIF_IN") (pintype "bidirectional"))
    )
    (net (code "32") (name "MOSI") (class "Default")
      (node (ref "IC7") (pin "5") (pinfunction "SDI_5") (pintype "bidirectional"))
      (node (ref "U$2") (pin "11-MOSI/CTX1") (pinfunction "11-MOSI/CTX1_11-MOSI/CTX1") (pintype "bidirectional"))
    )
    (net (code "33") (name "MUXA") (class "Default")
      (node (ref "IC1") (pin "11") (pinfunction "A_11") (pintype "input"))
      (node (ref "IC9") (pin "11") (pinfunction "A_11") (pintype "input"))
      (node (ref "U$2") (pin "29-TX7") (pinfunction "29-TX7_29-TX7") (pintype "bidirectional"))
    )
    (net (code "34") (name "MUXB") (class "Default")
      (node (ref "IC1") (pin "10") (pinfunction "B_10") (pintype "input"))
      (node (ref "IC9") (pin "10") (pinfunction "B_10") (pintype "input"))
      (node (ref "U$2") (pin "34-RX8") (pinfunction "34-RX8_34-RX8") (pintype "bidirectional"))
    )
    (net (code "35") (name "MUXC") (class "Default")
      (node (ref "IC1") (pin "9") (pinfunction "C_9") (pintype "input"))
      (node (ref "IC9") (pin "9") (pinfunction "C_9") (pintype "input"))
      (node (ref "U$2") (pin "35-TX8") (pinfunction "35/TX8_35-TX8") (pintype "bidirectional"))
    )
    (net (code "36") (name "MUXOUT1") (class "Default")
      (node (ref "IC9") (pin "3") (pinfunction "X_3") (pintype "bidirectional"))
    )
    (net (code "37") (name "MUXOUT2") (class "Default")
      (node (ref "IC1") (pin "3") (pinfunction "X_3") (pintype "bidirectional"))
    )
    (net (code "38") (name "Net-(IC1A-X0)") (class "Default")
      (node (ref "IC1") (pin "13") (pinfunction "X0_13") (pintype "bidirectional"))
      (node (ref "SW7") (pin "2") (pinfunction "2_2") (pintype "passive"))
    )
    (net (code "39") (name "Net-(IC1A-X1)") (class "Default")
      (node (ref "IC1") (pin "14") (pinfunction "X1_14") (pintype "bidirectional"))
      (node (ref "SW_RECORD") (pin "A2") (pinfunction "S1_A2") (pintype "passive"))
    )
    (net (code "40") (name "Net-(IC1A-X2)") (class "Default")
      (node (ref "IC1") (pin "15") (pinfunction "X2_15") (pintype "bidirectional"))
      (node (ref "SW_BLANK") (pin "A2") (pinfunction "S1_A2") (pintype "passive"))
    )
    (net (code "41") (name "Net-(IC1A-X4)") (class "Default")
      (node (ref "IC1") (pin "1") (pinfunction "X4_1") (pintype "bidirectional"))
      (node (ref "SW_RIGHT") (pin "A2") (pinfunction "S1_A2") (pintype "passive"))
    )
    (net (code "42") (name "Net-(IC2-VIN)") (class "Default")
      (node (ref "C12") (pin "+") (pinfunction "+_+") (pintype "passive"))
      (node (ref "IC2") (pin "2") (pinfunction "VIN_2") (pintype "input"))
      (node (ref "R7") (pin "1") (pinfunction "1_1") (pintype "passive"))
    )
    (net (code "43") (name "Net-(IC4A--IN)") (class "Default")
      (node (ref "IC4") (pin "2") (pinfunction "-IN_2") (pintype "input"))
      (node (ref "R30") (pin "1") (pinfunction "1_1") (pintype "passive"))
      (node (ref "R31") (pin "2") (pinfunction "2_2") (pintype "passive"))
    )
    (net (code "44") (name "Net-(IC4A-OUT)") (class "Default")
      (node (ref "IC4") (pin "1") (pinfunction "OUT_1") (pintype "output"))
      (node (ref "R16") (pin "1") (pinfunction "1_1") (pintype "passive"))
      (node (ref "R30") (pin "2") (pinfunction "2_2") (pintype "passive"))
    )
    (net (code "45") (name "Net-(IC4B--IN)") (class "Default")
      (node (ref "IC4") (pin "6") (pinfunction "-IN_6") (pintype "input"))
      (node (ref "IC4") (pin "7") (pinfunction "OUT_7") (pintype "output"))
      (node (ref "R35") (pin "1") (pinfunction "1_1") (pintype "passive"))
    )
    (net (code "46") (name "Net-(IC4C--IN)") (class "Default")
      (node (ref "IC4") (pin "9") (pinfunction "-IN_9") (pintype "input"))
      (node (ref "R32") (pin "1") (pinfunction "1_1") (pintype "passive"))
      (node (ref "R33") (pin "2") (pinfunction "2_2") (pintype "passive"))
    )
    (net (code "47") (name "Net-(IC4C-OUT)") (class "Default")
      (node (ref "IC4") (pin "8") (pinfunction "OUT_8") (pintype "output"))
      (node (ref "R24") (pin "1") (pinfunction "1_1") (pintype "passive"))
      (node (ref "R32") (pin "2") (pinfunction "2_2") (pintype "passive"))
    )
    (net (code "48") (name "Net-(IC4D--IN)") (class "Default")
      (node (ref "IC4") (pin "13") (pinfunction "-IN_13") (pintype "input"))
      (node (ref "IC4") (pin "14") (pinfunction "OUT_14") (pintype "output"))
      (node (ref "R21") (pin "1") (pinfunction "1_1") (pintype "passive"))
    )
    (net (code "49") (name "Net-(IC6A--IN)") (class "Default")
      (node (ref "C15") (pin "1") (pinfunction "1_1") (pintype "passive"))
      (node (ref "IC6") (pin "2") (pinfunction "-IN_2") (pintype "input"))
      (node (ref "R10") (pin "1") (pinfunction "1_1") (pintype "passive"))
      (node (ref "R8") (pin "1") (pinfunction "1_1") (pintype "passive"))
      (node (ref "R9") (pin "2") (pinfunction "2_2") (pintype "passive"))
    )
    (net (code "50") (name "Net-(IC6B--IN)") (class "Default")
      (node (ref "C13") (pin "1") (pinfunction "1_1") (pintype "passive"))
      (node (ref "IC6") (pin "6") (pinfunction "-IN_6") (pintype "input"))
      (node (ref "R11") (pin "1") (pinfunction "1_1") (pintype "passive"))
      (node (ref "R13") (pin "2") (pinfunction "2_2") (pintype "passive"))
      (node (ref "R14") (pin "1") (pinfunction "1_1") (pintype "passive"))
    )
    (net (code "51") (name "Net-(IC7-VOUTA)") (class "Default")
      (node (ref "IC7") (pin "14") (pinfunction "VOUTA_14") (pintype "bidirectional"))
      (node (ref "JP4") (pin "1") (pinfunction "1_1") (pintype "passive"))
    )
    (net (code "52") (name "Net-(IC7-VOUTB)") (class "Default")
      (node (ref "IC7") (pin "10") (pinfunction "VOUTB_10") (pintype "bidirectional"))
      (node (ref "JP3") (pin "1") (pinfunction "1_1") (pintype "passive"))
    )
    (net (code "53") (name "Net-(IC8A--IN)") (class "Default")
      (node (ref "C14") (pin "1") (pinfunction "1_1") (pintype "passive"))
      (node (ref "IC8") (pin "2") (pinfunction "-IN_2") (pintype "input"))
      (node (ref "R36") (pin "1") (pinfunction "1_1") (pintype "passive"))
      (node (ref "R37") (pin "2") (pinfunction "2_2") (pintype "passive"))
      (node (ref "R38") (pin "1") (pinfunction "1_1") (pintype "passive"))
    )
    (net (code "54") (name "Net-(IC8B--IN)") (class "Default")
      (node (ref "C16") (pin "1") (pinfunction "1_1") (pintype "passive"))
      (node (ref "IC8") (pin "6") (pinfunction "-IN_6") (pintype "input"))
      (node (ref "R39") (pin "1") (pinfunction "1_1") (pintype "passive"))
      (node (ref "R40") (pin "2") (pinfunction "2_2") (pintype "passive"))
      (node (ref "R41") (pin "1") (pinfunction "1_1") (pintype "passive"))
    )
    (net (code "55") (name "Net-(IC9A-X0)") (class "Default")
      (node (ref "IC9") (pin "13") (pinfunction "X0_13") (pintype "bidirectional"))
      (node (ref "P_RED") (pin "P$2") (pinfunction "S_P$2") (pintype "passive"))
    )
    (net (code "56") (name "Net-(IC9A-X1)") (class "Default")
      (node (ref "IC9") (pin "14") (pinfunction "X1_14") (pintype "bidirectional"))
      (node (ref "P_BLUE") (pin "P$2") (pinfunction "S_P$2") (pintype "passive"))
    )
    (net (code "57") (name "Net-(IC9A-X2)") (class "Default")
      (node (ref "IC9") (pin "15") (pinfunction "X2_15") (pintype "bidirectional"))
      (node (ref "P_GREEN") (pin "P$2") (pinfunction "S_P$2") (pintype "passive"))
    )
    (net (code "58") (name "Net-(IC9A-X3)") (class "Default")
      (node (ref "IC9") (pin "12") (pinfunction "X3_12") (pintype "bidirectional"))
      (node (ref "P_X") (pin "P$2") (pinfunction "S_P$2") (pintype "passive"))
    )
    (net (code "59") (name "Net-(IC9A-X4)") (class "Default")
      (node (ref "IC9") (pin "1") (pinfunction "X4_1") (pintype "bidirectional"))
      (node (ref "P_Y") (pin "P$2") (pinfunction "S_P$2") (pintype "passive"))
    )
    (net (code "60") (name "Net-(IC9A-X5)") (class "Default")
      (node (ref "IC9") (pin "5") (pinfunction "X5_5") (pintype "bidirectional"))
      (node (ref "P_MODA") (pin "P$2") (pinfunction "S_P$2") (pintype "passive"))
    )
    (net (code "61") (name "Net-(IC9A-X6)") (class "Default")
      (node (ref "IC9") (pin "2") (pinfunction "X6_2") (pintype "bidirectional"))
      (node (ref "P_MODB") (pin "P$2") (pinfunction "S_P$2") (pintype "passive"))
    )
    (net (code "62") (name "Net-(IC9A-X7)") (class "Default")
      (node (ref "IC9") (pin "4") (pinfunction "X7_4") (pintype "bidirectional"))
      (node (ref "P_SAMPLE") (pin "P$2") (pinfunction "S_P$2") (pintype "passive"))
    )
    (net (code "63") (name "Net-(IC10C--IN)") (class "Default")
      (node (ref "IC10") (pin "8") (pinfunction "OUT_8") (pintype "output"))
      (node (ref "IC10") (pin "9") (pinfunction "-IN_9") (pintype "input"))
      (node (ref "R18") (pin "1") (pinfunction "1_1") (pintype "passive"))
    )
    (net (code "64") (name "Net-(IC10D--IN)") (class "Default")
      (node (ref "IC10") (pin "13") (pinfunction "-IN_13") (pintype "input"))
      (node (ref "IC10") (pin "14") (pinfunction "OUT_14") (pintype "output"))
    )
    (net (code "65") (name "Net-(JP1-Pad1)") (class "Default")
      (node (ref "JP1") (pin "1") (pinfunction "1_1") (pintype "passive"))
      (node (ref "JP1") (pin "2") (pinfunction "2_2") (pintype "passive"))
      (node (ref "P2") (pin "2") (pinfunction "2_2") (pintype "bidirectional"))
    )
    (net (code "66") (name "Net-(JP1-Pad10)") (class "Default")
      (node (ref "JP1") (pin "10") (pinfunction "10_10") (pintype "passive"))
      (node (ref "JP1") (pin "9") (pinfunction "9_9") (pintype "passive"))
      (node (ref "P1") (pin "2") (pinfunction "2_2") (pintype "bidirectional"))
    )
    (net (code "67") (name "Net-(JP1-Pad11)") (class "Default")
      (node (ref "JP1") (pin "11") (pinfunction "11_11") (pintype "passive"))
      (node (ref "JP1") (pin "12") (pinfunction "12_12") (pintype "passive"))
      (node (ref "P3") (pin "2") (pinfunction "2_2") (pintype "bidirectional"))
    )
    (net (code "68") (name "Net-(J_BLUE-3)") (class "Default")
      (node (ref "J_BLUE") (pin "P3") (pinfunction "3_P3") (pintype "passive"))
      (node (ref "R46") (pin "1") (pinfunction "1_1") (pintype "passive"))
    )
    (net (code "69") (name "Net-(J_GREEN-3)") (class "Default")
      (node (ref "J_GREEN") (pin "P3") (pinfunction "3_P3") (pintype "passive"))
      (node (ref "R44") (pin "1") (pinfunction "1_1") (pintype "passive"))
    )
    (net (code "70") (name "Net-(J_RED-3)") (class "Default")
      (node (ref "J_RED") (pin "P3") (pinfunction "3_P3") (pintype "passive"))
      (node (ref "R42") (pin "1") (pinfunction "1_1") (pintype "passive"))
    )
    (net (code "71") (name "Net-(MOD_A-3)") (class "Default")
      (node (ref "MOD_A") (pin "P3") (pinfunction "3_P3") (pintype "passive"))
      (node (ref "R36") (pin "2") (pinfunction "2_2") (pintype "passive"))
    )
    (net (code "72") (name "Net-(MOD_B-3)") (class "Default")
      (node (ref "MOD_B") (pin "P3") (pinfunction "3_P3") (pintype "passive"))
      (node (ref "R39") (pin "2") (pinfunction "2_2") (pintype "passive"))
    )
    (net (code "73") (name "Net-(Q1-PadB)") (class "Default")
      (node (ref "Q1") (pin "B") (pinfunction "B_B") (pintype "passive"))
      (node (ref "R44") (pin "2") (pinfunction "2_2") (pintype "passive"))
    )
    (net (code "74") (name "Net-(Q2-PadB)") (class "Default")
      (node (ref "Q2") (pin "B") (pinfunction "B_B") (pintype "passive"))
      (node (ref "R42") (pin "2") (pinfunction "2_2") (pintype "passive"))
    )
    (net (code "75") (name "Net-(Q3-PadB)") (class "Default")
      (node (ref "Q3") (pin "B") (pinfunction "B_B") (pintype "passive"))
      (node (ref "R46") (pin "2") (pinfunction "2_2") (pintype "passive"))
    )
    (net (code "76") (name "Net-(U$2-5V)") (class "Default")
      (node (ref "U$2") (pin "+5V") (pinfunction "5V_+5V") (pintype "bidirectional"))
      (node (ref "X2") (pin "1") (pinfunction "1_1") (pintype "passive"))
    )
    (net (code "77") (name "Net-(U$2-PadDM)") (class "Default")
      (node (ref "U$2") (pin "DM") (pinfunction "DM_DM") (pintype "bidirectional"))
      (node (ref "X2") (pin "2") (pinfunction "2_2") (pintype "passive"))
    )
    (net (code "78") (name "Net-(U$2-PadDP)") (class "Default")
      (node (ref "U$2") (pin "DP") (pinfunction "DP_DP") (pintype "bidirectional"))
      (node (ref "X2") (pin "3") (pinfunction "3_3") (pintype "passive"))
    )
    (net (code "79") (name "Net-(U$2-PadGND4)") (class "Default")
      (node (ref "U$2") (pin "GND4") (pinfunction "GND4_GND4") (pintype "bidirectional"))
      (node (ref "X2") (pin "4") (pinfunction "4_4") (pintype "passive"))
    )
    (net (code "80") (name "Net-(U1A-+IN)") (class "Default")
      (node (ref "JP4") (pin "2") (pinfunction "2_2") (pintype "passive"))
      (node (ref "U1") (pin "3") (pinfunction "+IN_3") (pintype "input"))
    )
    (net (code "81") (name "Net-(U1A--IN)") (class "Default")
      (node (ref "R26") (pin "2") (pinfunction "2_2") (pintype "passive"))
      (node (ref "R27") (pin "1") (pinfunction "1_1") (pintype "passive"))
      (node (ref "U1") (pin "2") (pinfunction "-IN_2") (pintype "input"))
    )
    (net (code "82") (name "Net-(U1B-+IN)") (class "Default")
      (node (ref "JP3") (pin "2") (pinfunction "2_2") (pintype "passive"))
      (node (ref "U1") (pin "5") (pinfunction "+IN_5") (pintype "input"))
    )
    (net (code "83") (name "Net-(U1B--IN)") (class "Default")
      (node (ref "R28") (pin "2") (pinfunction "2_2") (pintype "passive"))
      (node (ref "R29") (pin "1") (pinfunction "1_1") (pintype "passive"))
      (node (ref "U1") (pin "6") (pinfunction "-IN_6") (pintype "input"))
    )
    (net (code "84") (name "Net-(VR1-CW_1)") (class "Default")
      (node (ref "R11") (pin "2") (pinfunction "2_2") (pintype "passive"))
      (node (ref "VR1") (pin "A3") (pinfunction "CW_1_A3") (pintype "bidirectional"))
    )
    (net (code "85") (name "Net-(VR1-CW_2)") (class "Default")
      (node (ref "R8") (pin "2") (pinfunction "2_2") (pintype "passive"))
      (node (ref "VR1") (pin "B3") (pinfunction "CW_2_B3") (pintype "bidirectional"))
    )
    (net (code "86") (name "Net-(VR1-WIPER_1)") (class "Default")
      (node (ref "VR1") (pin "A2") (pinfunction "WIPER_1_A2") (pintype "bidirectional"))
      (node (ref "Y_IN") (pin "P3") (pinfunction "3_P3") (pintype "passive"))
    )
    (net (code "87") (name "Net-(VR1-WIPER_2)") (class "Default")
      (node (ref "VR1") (pin "B2") (pinfunction "WIPER_2_B2") (pintype "bidirectional"))
      (node (ref "X_IN") (pin "P3") (pinfunction "3_P3") (pintype "passive"))
    )
    (net (code "88") (name "OUTGND") (class "Default")
      (node (ref "J1") (pin "4") (pinfunction "4_4") (pintype "passive"))
    )
    (net (code "89") (name "OUTL") (class "Default")
      (node (ref "J1") (pin "5") (pinfunction "5_5") (pintype "passive"))
      (node (ref "JP4") (pin "3") (pinfunction "3_3") (pintype "passive"))
    )
    (net (code "90") (name "OUTR") (class "Default")
      (node (ref "J1") (pin "3") (pinfunction "3_3") (pintype "passive"))
      (node (ref "JP3") (pin "3") (pinfunction "3_3") (pintype "passive"))
    )
    (net (code "91") (name "R+") (class "Default")
      (node (ref "R20") (pin "2") (pinfunction "2_2") (pintype "passive"))
      (node (ref "X1") (pin "5") (pinfunction "5_5") (pintype "passive"))
    )
    (net (code "92") (name "R1+") (class "Default")
      (node (ref "IC10") (pin "1") (pinfunction "OUT_1") (pintype "output"))
      (node (ref "IC10") (pin "2") (pinfunction "-IN_2") (pintype "input"))
      (node (ref "R20") (pin "1") (pinfunction "1_1") (pintype "passive"))
    )
    (net (code "93") (name "RX_DOUT") (class "Default")
      (node (ref "U$2") (pin "8-TX2/IN1") (pinfunction "8-TX2/IN1_8-TX2/IN1") (pintype "bidirectional"))
    )
    (net (code "94") (name "SCK") (class "Default")
      (node (ref "IC7") (pin "4") (pinfunction "SCK_4") (pintype "bidirectional"))
      (node (ref "U$2") (pin "13-SCK/LED") (pinfunction "13-SCK/LED_13-SCK/LED") (pintype "bidirectional"))
    )
    (net (code "95") (name "SCL") (class "Default")
      (node (ref "U$2") (pin "19-A5/SCL0") (pinfunction "19-A5/SCL0_19-A5/SCL0") (pintype "bidirectional"))
      (node (ref "U$3") (pin "3") (pinfunction "SCL_3") (pintype "bidirectional"))
    )
    (net (code "96") (name "SDA") (class "Default")
      (node (ref "U$2") (pin "18-A4/SDA0") (pinfunction "18-A4/SDA0_18-A4/SDA0") (pintype "bidirectional"))
      (node (ref "U$3") (pin "4") (pinfunction "SDA_4") (pintype "bidirectional"))
    )
    (net (code "97") (name "SHUTTER") (class "Default")
      (node (ref "X1") (pin "13") (pinfunction "13_13") (pintype "passive"))
    )
    (net (code "98") (name "SS") (class "Default")
      (node (ref "IC7") (pin "3") (pinfunction "~{CS}_3") (pintype "bidirectional"))
      (node (ref "U$2") (pin "10-CS\\MQSR") (pinfunction "10-CS/MQSR_10-CS\\MQSR") (pintype "bidirectional"))
    )
    (net (code "99") (name "T26") (class "Default")
      (node (ref "Q2") (pin "C") (pinfunction "C_C") (pintype "passive"))
      (node (ref "R43") (pin "1") (pinfunction "1_1") (pintype "passive"))
      (node (ref "U$2") (pin "26-A12/MOSI1") (pinfunction "26-A12/MOSI1_26-A12/MOSI1") (pintype "bidirectional"))
    )
    (net (code "100") (name "T27") (class "Default")
      (node (ref "Q1") (pin "C") (pinfunction "C_C") (pintype "passive"))
      (node (ref "R45") (pin "1") (pinfunction "1_1") (pintype "passive"))
      (node (ref "U$2") (pin "27-A13/SCK1") (pinfunction "27-A13/SCK1_27-A13/SCK1") (pintype "bidirectional"))
    )
    (net (code "101") (name "T30") (class "Default")
      (node (ref "U$2") (pin "30-CRX3") (pinfunction "30-CRX3_30-CRX3") (pintype "bidirectional"))
    )
    (net (code "102") (name "T38") (class "Default")
      (node (ref "IC1") (pin "12") (pinfunction "X3_12") (pintype "bidirectional"))
      (node (ref "IC1") (pin "2") (pinfunction "X6_2") (pintype "bidirectional"))
      (node (ref "Q3") (pin "C") (pinfunction "C_C") (pintype "passive"))
      (node (ref "R47") (pin "1") (pinfunction "1_1") (pintype "passive"))
      (node (ref "SW_DOWN") (pin "A1") (pinfunction "S_A1") (pintype "passive"))
      (node (ref "SW_DOWN") (pin "A2") (pinfunction "S1_A2") (pintype "passive"))
      (node (ref "SW_PLAY") (pin "A1") (pinfunction "S_A1") (pintype "passive"))
      (node (ref "SW_PLAY") (pin "A2") (pinfunction "S1_A2") (pintype "passive"))
      (node (ref "U$2") (pin "38-A14/CS/IN1") (pinfunction "38-A14/CS/IN1_38-A14/CS/IN1") (pintype "bidirectional"))
    )
    (net (code "103") (name "T39") (class "Default")
      (node (ref "IC1") (pin "4") (pinfunction "X7_4") (pintype "bidirectional"))
      (node (ref "IC1") (pin "5") (pinfunction "X5_5") (pintype "bidirectional"))
      (node (ref "SW_LEFT") (pin "A1") (pinfunction "S_A1") (pintype "passive"))
      (node (ref "SW_LEFT") (pin "A2") (pinfunction "S1_A2") (pintype "passive"))
      (node (ref "SW_RIGHT") (pin "A1") (pinfunction "S_A1") (pintype "passive"))
      (node (ref "SW_UP") (pin "A1") (pinfunction "S_A1") (pintype "passive"))
      (node (ref "SW_UP") (pin "A2") (pinfunction "S1_A2") (pintype "passive"))
      (node (ref "U$2") (pin "39-A15/CS/OUT1A") (pinfunction "39-A15/CS/OUT1A_39-A15/CS/OUT1A") (pintype "bidirectional"))
    )
    (net (code "104") (name "TB") (class "Default")
      (node (ref "IC10") (pin "10") (pinfunction "+IN_10") (pintype "input"))
      (node (ref "R22") (pin "2") (pinfunction "2_2") (pintype "passive"))
      (node (ref "U$2") (pin "2-OUT2") (pinfunction "2-OUT2_2-OUT2") (pintype "bidirectional"))
    )
    (net (code "105") (name "TG") (class "Default")
      (node (ref "IC10") (pin "5") (pinfunction "+IN_5") (pintype "input"))
      (node (ref "R23") (pin "2") (pinfunction "2_2") (pintype "passive"))
      (node (ref "U$2") (pin "9-OUT1C") (pinfunction "9-OUT1C_9-OUT1C") (pintype "bidirectional"))
    )
    (net (code "106") (name "TR") (class "Default")
      (node (ref "IC10") (pin "3") (pinfunction "+IN_3") (pintype "input"))
      (node (ref "R25") (pin "2") (pinfunction "2_2") (pintype "passive"))
      (node (ref "U$2") (pin "32-OUT1B") (pinfunction "32-OUT1B_32-OUT1B") (pintype "bidirectional"))
    )
    (net (code "107") (name "TX_DIN") (class "Default")
      (node (ref "U$2") (pin "7-RX2/OUT1A") (pinfunction "7-RX2/OUT1A_7-RX2/OUT1A") (pintype "bidirectional"))
    )
    (net (code "108") (name "VCC") (class "Default")
      (node (ref "R7") (pin "2") (pinfunction "2_2") (pintype "passive"))
    )
    (net (code "109") (name "VEE") (class "Default")
      (node (ref "R12") (pin "1") (pinfunction "1_1") (pintype "passive"))
    )
    (net (code "110") (name "X+") (class "Default")
      (node (ref "R35") (pin "2") (pinfunction "2_2") (pintype "passive"))
      (node (ref "X1") (pin "1") (pinfunction "1_1") (pintype "passive"))
    )
    (net (code "111") (name "X-") (class "Default")
      (node (ref "R24") (pin "2") (pinfunction "2_2") (pintype "passive"))
      (node (ref "X1") (pin "14") (pinfunction "14_14") (pintype "passive"))
    )
    (net (code "112") (name "X2") (class "Default")
      (node (ref "IC4") (pin "5") (pinfunction "+IN_5") (pintype "input"))
      (node (ref "R27") (pin "2") (pinfunction "2_2") (pintype "passive"))
      (node (ref "R33") (pin "1") (pinfunction "1_1") (pintype "passive"))
      (node (ref "U1") (pin "1") (pinfunction "OUT_1") (pintype "output"))
    )
    (net (code "113") (name "X_IN") (class "Default")
      (node (ref "C15") (pin "2") (pinfunction "2_2") (pintype "passive"))
      (node (ref "IC6") (pin "1") (pinfunction "OUT_1") (pintype "output"))
      (node (ref "R9") (pin "1") (pinfunction "1_1") (pintype "passive"))
      (node (ref "U$2") (pin "17-A3/TX4/SDA1") (pinfunction "17-A3/TX4/SDA1_17-A3/TX4/SDA1") (pintype "bidirectional"))
    )
    (net (code "114") (name "Y+") (class "Default")
      (node (ref "R21") (pin "2") (pinfunction "2_2") (pintype "passive"))
      (node (ref "X1") (pin "2") (pinfunction "2_2") (pintype "passive"))
    )
    (net (code "115") (name "Y-") (class "Default")
      (node (ref "R16") (pin "2") (pinfunction "2_2") (pintype "passive"))
      (node (ref "X1") (pin "15") (pinfunction "15_15") (pintype "passive"))
    )
    (net (code "116") (name "Y2") (class "Default")
      (node (ref "IC4") (pin "12") (pinfunction "+IN_12") (pintype "input"))
      (node (ref "R29") (pin "2") (pinfunction "2_2") (pintype "passive"))
      (node (ref "R31") (pin "1") (pinfunction "1_1") (pintype "passive"))
      (node (ref "U1") (pin "7") (pinfunction "OUT_7") (pintype "output"))
    )
    (net (code "117") (name "Y_IN") (class "Default")
      (node (ref "C13") (pin "2") (pinfunction "2_2") (pintype "passive"))
      (node (ref "IC6") (pin "7") (pinfunction "OUT_7") (pintype "output"))
      (node (ref "R13") (pin "1") (pinfunction "1_1") (pintype "passive"))
      (node (ref "U$2") (pin "16-A2/RX4/SCL1") (pinfunction "16-A2/RX4/SCL1_16-A2/RX4/SCL1") (pintype "bidirectional"))
    )
    (net (code "118") (name "unconnected-(IC7-NC_1-Pad2)") (class "Default")
      (node (ref "IC7") (pin "2") (pinfunction "NC_1_2") (pintype "bidirectional"))
    )
    (net (code "119") (name "unconnected-(IC7-NC_2-Pad6)") (class "Default")
      (node (ref "IC7") (pin "6") (pinfunction "NC_2_6") (pintype "bidirectional"))
    )
    (net (code "120") (name "unconnected-(IC7-NC_3-Pad7)") (class "Default")
      (node (ref "IC7") (pin "7") (pinfunction "NC_3_7") (pintype "bidirectional"))
    )
    (net (code "121") (name "unconnected-(JP1-Pad13)") (class "Default")
      (node (ref "JP1") (pin "13") (pinfunction "13_13") (pintype "passive"))
    )
    (net (code "122") (name "unconnected-(JP1-Pad14)") (class "Default")
      (node (ref "JP1") (pin "14") (pinfunction "14_14") (pintype "passive"))
    )
    (net (code "123") (name "unconnected-(JP1-Pad15)") (class "Default")
      (node (ref "JP1") (pin "15") (pinfunction "15_15") (pintype "passive"))
    )
    (net (code "124") (name "unconnected-(JP1-Pad16)") (class "Default")
      (node (ref "JP1") (pin "16") (pinfunction "16_16") (pintype "passive"))
    )
    (net (code "125") (name "unconnected-(JP2-Pad1)") (class "Default")
      (node (ref "JP2") (pin "1") (pinfunction "1_1") (pintype "passive"))
    )
    (net (code "126") (name "unconnected-(J_BLUE-2-PadP2)") (class "Default")
      (node (ref "J_BLUE") (pin "P2") (pinfunction "2_P2") (pintype "passive"))
    )
    (net (code "127") (name "unconnected-(J_GREEN-2-PadP2)") (class "Default")
      (node (ref "J_GREEN") (pin "P2") (pinfunction "2_P2") (pintype "passive"))
    )
    (net (code "128") (name "unconnected-(J_RED-2-PadP2)") (class "Default")
      (node (ref "J_RED") (pin "P2") (pinfunction "2_P2") (pintype "passive"))
    )
    (net (code "129") (name "unconnected-(SW_BLANK-P-PadB1)") (class "Default")
      (node (ref "SW_BLANK") (pin "B1") (pinfunction "P_B1") (pintype "passive"))
    )
    (net (code "130") (name "unconnected-(SW_BLANK-S-PadA1)") (class "Default")
      (node (ref "SW_BLANK") (pin "A1") (pinfunction "S_A1") (pintype "passive"))
    )
    (net (code "131") (name "unconnected-(SW_RECORD-P-PadB1)") (class "Default")
      (node (ref "SW_RECORD") (pin "B1") (pinfunction "P_B1") (pintype "passive"))
    )
    (net (code "132") (name "unconnected-(SW_RECORD-S-PadA1)") (class "Default")
      (node (ref "SW_RECORD") (pin "A1") (pinfunction "S_A1") (pintype "passive"))
    )
    (net (code "133") (name "unconnected-(SW_RIGHT-P-PadB1)") (class "Default")
      (node (ref "SW_RIGHT") (pin "B1") (pinfunction "P_B1") (pintype "passive"))
    )
    (net (code "134") (name "unconnected-(U$2-Pad0-RX1{slash}CS1{slash}CRX2)") (class "Default")
      (node (ref "U$2") (pin "0-RX1/CS1/CRX2") (pinfunction "0-RX1/CS1/CRX2_0-RX1/CS1/CRX2") (pintype "bidirectional"))
    )
    (net (code "135") (name "unconnected-(U$2-Pad1-TX1{slash}MISO1{slash}CTX2)") (class "Default")
      (node (ref "U$2") (pin "1-TX1/MISO1/CTX2") (pinfunction "1-TX1/MISO1/CTX2_1-TX1/MISO1/CTX2") (pintype "bidirectional"))
    )
    (net (code "136") (name "unconnected-(U$2-Pad3-LRCLK2)") (class "Default")
      (node (ref "U$2") (pin "3-LRCLK2") (pinfunction "3-LRCLK2_3-LRCLK2") (pintype "bidirectional"))
    )
    (net (code "137") (name "unconnected-(U$2-Pad3V3-2)") (class "Default")
      (node (ref "U$2") (pin "3V3-2") (pinfunction "3V3-2_3V3-2") (pintype "bidirectional"))
    )
    (net (code "138") (name "unconnected-(U$2-Pad3V3-3)") (class "Default")
      (node (ref "U$2") (pin "3V3-3") (pinfunction "3V3-3_3V3-3") (pintype "bidirectional"))
    )
    (net (code "139") (name "unconnected-(U$2-Pad4-BCLK2)") (class "Default")
      (node (ref "U$2") (pin "4-BCLK2") (pinfunction "4-BCLK2_4-BCLK2") (pintype "bidirectional"))
    )
    (net (code "140") (name "unconnected-(U$2-Pad5-IN2)") (class "Default")
      (node (ref "U$2") (pin "5-IN2") (pinfunction "5-IN2_5-IN2") (pintype "bidirectional"))
    )
    (net (code "141") (name "unconnected-(U$2-Pad6-OUT1D)") (class "Default")
      (node (ref "U$2") (pin "6-OUT1D") (pinfunction "6-OUT1D_6-OUT1D") (pintype "bidirectional"))
    )
    (net (code "142") (name "unconnected-(U$2-Pad22-A8{slash}CTX1)") (class "Default")
      (node (ref "U$2") (pin "22-A8/CTX1") (pinfunction "22-A8/CTX1_22-A8/CTX1") (pintype "bidirectional"))
    )
    (net (code "143") (name "unconnected-(U$2-Pad24-A10{slash}TX6{slash}SCL2)") (class "Default")
      (node (ref "U$2") (pin "24-A10/TX6/SCL2") (pinfunction "24-A10/TX6/SCL2_24-A10/TX6/SCL2") (pintype "bidirectional"))
    )
    (net (code "144") (name "unconnected-(U$2-Pad25-A11{slash}RX6{slash}SDA2)") (class "Default")
      (node (ref "U$2") (pin "25-A11/RX6/SDA2") (pinfunction "25-A11/RX6/SDA2_25-A11/RX6/SDA2") (pintype "bidirectional"))
    )
    (net (code "145") (name "unconnected-(U$2-Pad33-MCLK2)") (class "Default")
      (node (ref "U$2") (pin "33-MCLK2") (pinfunction "33-MCLK2_33-MCLK2") (pintype "bidirectional"))
    )
    (net (code "146") (name "unconnected-(U$2-Pad36-PWM)") (class "Default")
      (node (ref "U$2") (pin "36-PWM") (pinfunction "36-PWM_36-PWM") (pintype "bidirectional"))
    )
    (net (code "147") (name "unconnected-(U$2-Pad37-PWM)") (class "Default")
      (node (ref "U$2") (pin "37-PWM") (pinfunction "37-PWM_37-PWM") (pintype "bidirectional"))
    )
    (net (code "148") (name "unconnected-(U$2-PadGND1)") (class "Default")
      (node (ref "U$2") (pin "GND1") (pinfunction "GND1_GND1") (pintype "bidirectional"))
    )
    (net (code "149") (name "unconnected-(U$2-PadGND2)") (class "Default")
      (node (ref "U$2") (pin "GND2") (pinfunction "GND2_GND2") (pintype "bidirectional"))
    )
    (net (code "150") (name "unconnected-(U$2-PadGND3)") (class "Default")
      (node (ref "U$2") (pin "GND3") (pinfunction "GND3_GND3") (pintype "bidirectional"))
    )
    (net (code "151") (name "unconnected-(U$2-PadGND5)") (class "Default")
      (node (ref "U$2") (pin "GND5") (pinfunction "GND5_GND5") (pintype "bidirectional"))
    )
    (net (code "152") (name "unconnected-(U$2-PadGND6)") (class "Default")
      (node (ref "U$2") (pin "GND6") (pinfunction "GND6_GND6") (pintype "bidirectional"))
    )
    (net (code "153") (name "unconnected-(U$2-PadON{slash}OFF)") (class "Default")
      (node (ref "U$2") (pin "ON/OFF") (pinfunction "ON/OFF_ON/OFF") (pintype "bidirectional"))
    )
    (net (code "154") (name "unconnected-(U$2-PadPROGRAM)") (class "Default")
      (node (ref "U$2") (pin "PROGRAM") (pinfunction "PROGRAM_PROGRAM") (pintype "bidirectional"))
    )
    (net (code "155") (name "unconnected-(U$2-PadVBAT)") (class "Default")
      (node (ref "U$2") (pin "VBAT") (pinfunction "VBAT_VBAT") (pintype "bidirectional"))
    )
    (net (code "156") (name "unconnected-(U$2-PadVUSB)") (class "Default")
      (node (ref "U$2") (pin "VUSB") (pinfunction "VUSB_VUSB") (pintype "bidirectional"))
    )
    (net (code "157") (name "unconnected-(X1-Pad8)") (class "Default")
      (node (ref "X1") (pin "8") (pinfunction "8_8") (pintype "passive"))
    )
    (net (code "158") (name "unconnected-(X1-Pad9)") (class "Default")
      (node (ref "X1") (pin "9") (pinfunction "9_9") (pintype "passive"))
    )
    (net (code "159") (name "unconnected-(X1-Pad10)") (class "Default")
      (node (ref "X1") (pin "10") (pinfunction "10_10") (pintype "passive"))
    )
    (net (code "160") (name "unconnected-(X1-Pad11)") (class "Default")
      (node (ref "X1") (pin "11") (pinfunction "11_11") (pintype "passive"))
    )
    (net (code "161") (name "unconnected-(X1-Pad12)") (class "Default")
      (node (ref "X1") (pin "12") (pinfunction "12_12") (pintype "passive"))
    )
    (net (code "162") (name "unconnected-(X1-Pad21)") (class "Default")
      (node (ref "X1") (pin "21") (pinfunction "21_21") (pintype "passive"))
    )
    (net (code "163") (name "unconnected-(X1-Pad22)") (class "Default")
      (node (ref "X1") (pin "22") (pinfunction "22_22") (pintype "passive"))
    )
    (net (code "164") (name "unconnected-(X1-Pad23)") (class "Default")
      (node (ref "X1") (pin "23") (pinfunction "23_23") (pintype "passive"))
    )
    (net (code "165") (name "unconnected-(X1-Pad24)") (class "Default")
      (node (ref "X1") (pin "24") (pinfunction "24_24") (pintype "passive"))
    )
    (net (code "166") (name "~{LDAC}") (class "Default")
      (node (ref "IC7") (pin "8") (pinfunction "~{LDAC}_8") (pintype "bidirectional"))
    )
  )
)
